# FPGA.net
KiCad netlist of a schematic drawn in Altium Designer
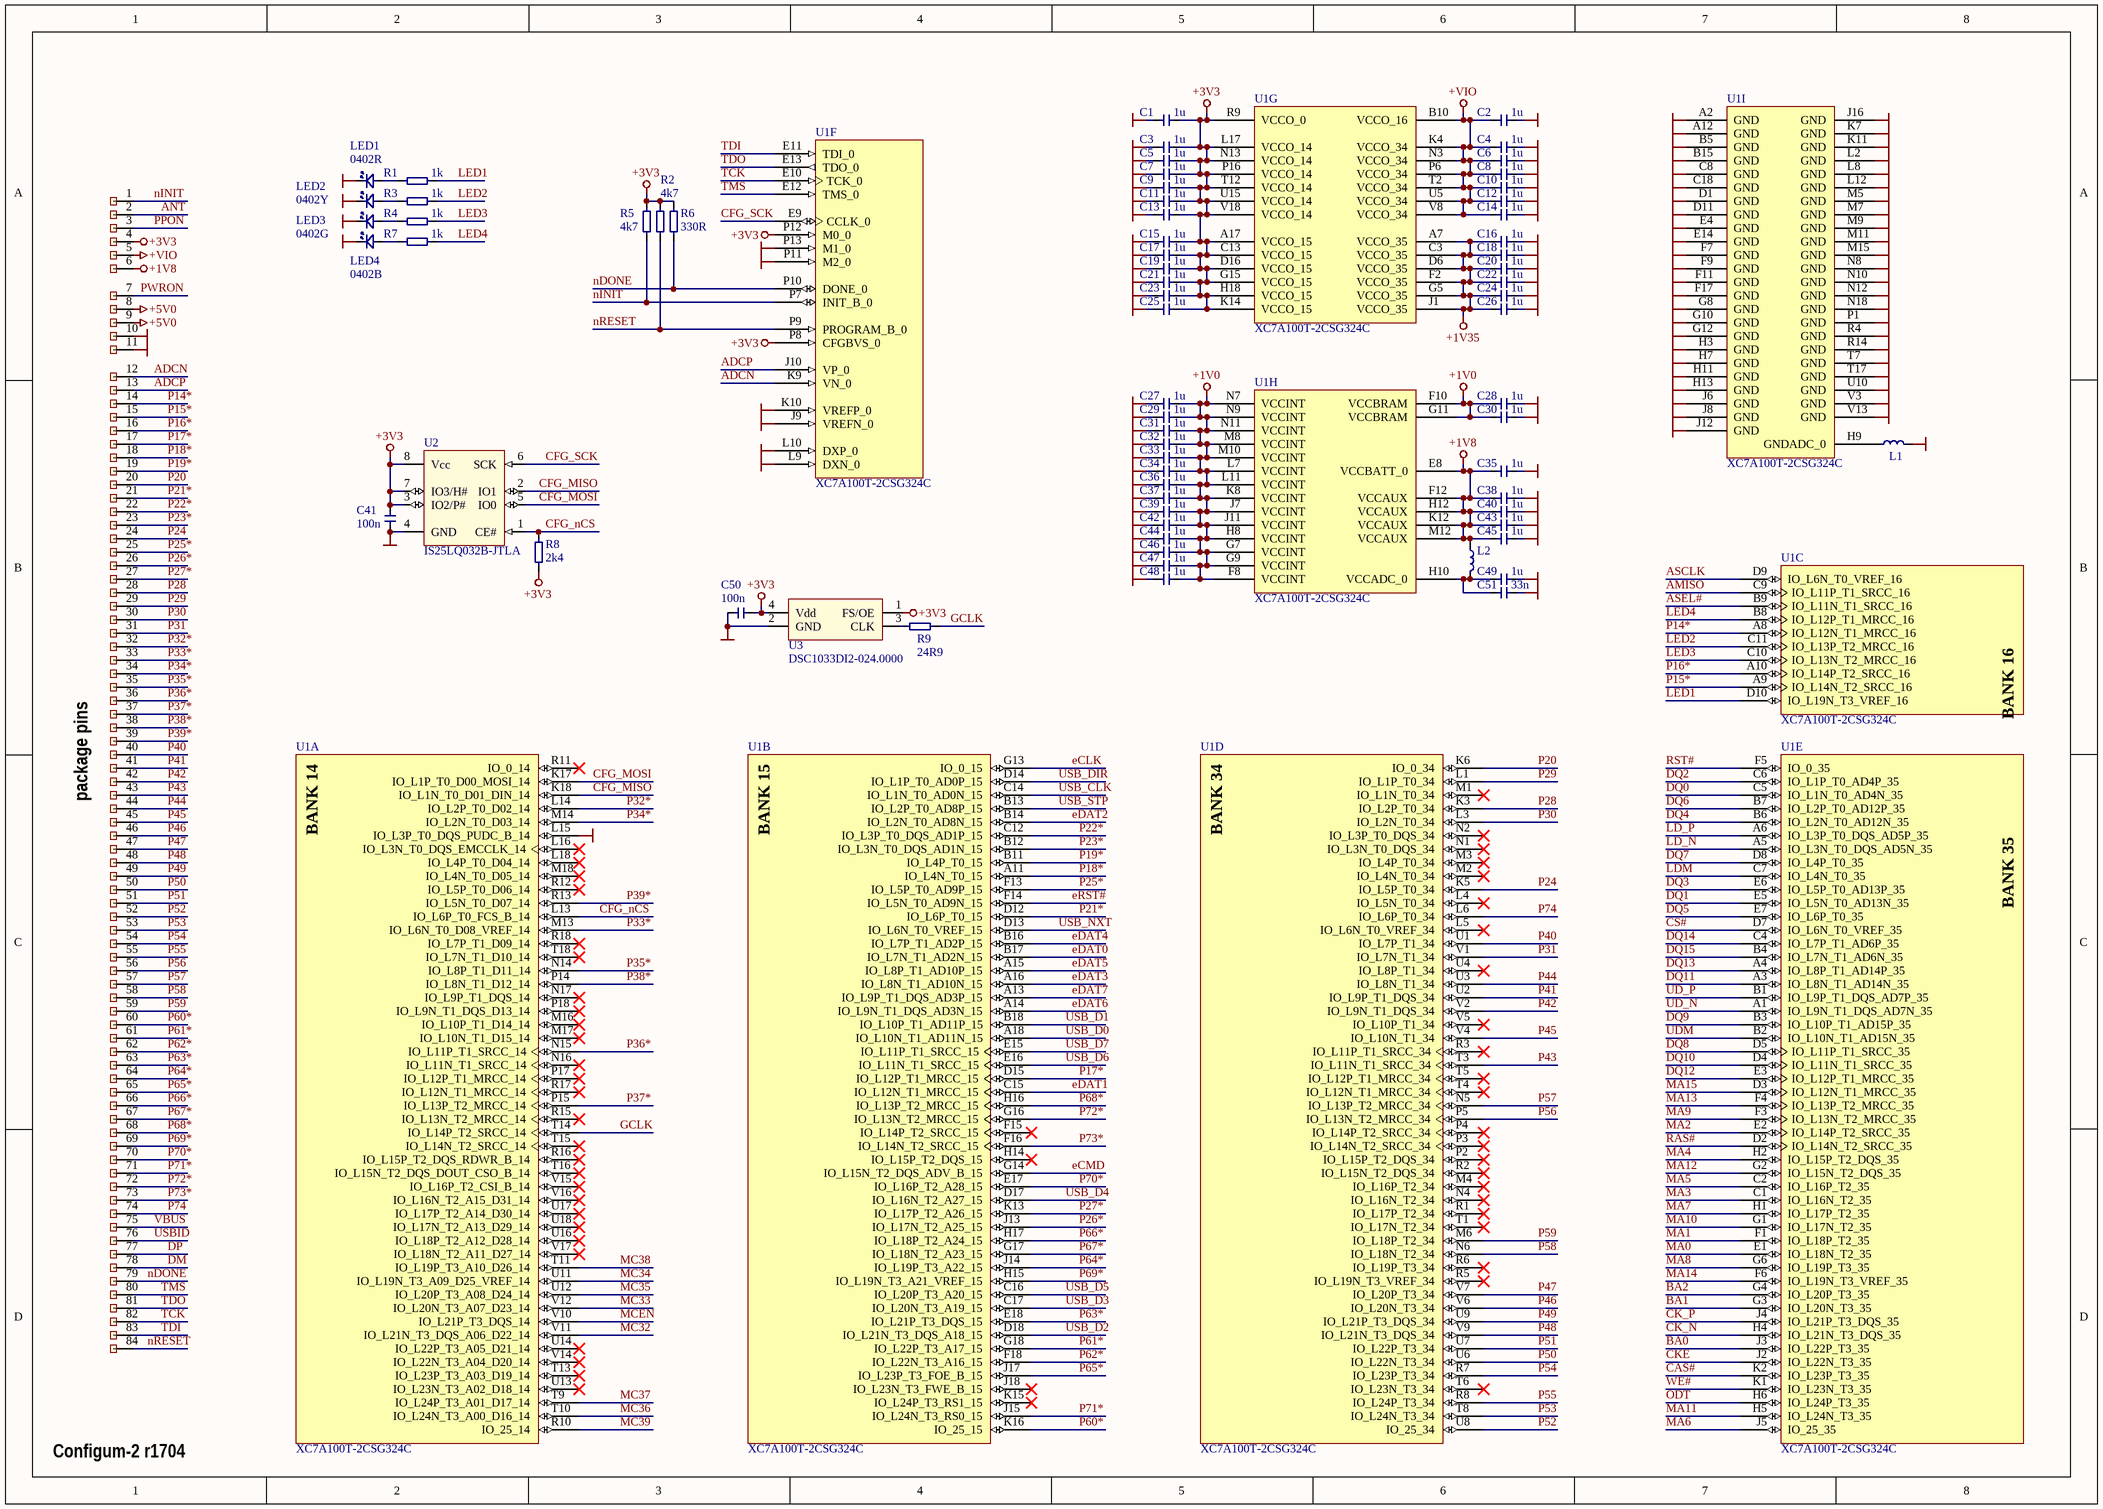
[diagram p0: FPGA.SchDoc]

(export (version "E")
  (design (tool "Eeschema 10.0.6"))
  (components
    (comp (ref "C1")
      (value "1u")
      (footprint "_0201")
      (description "Capacitor")
      (libsource (lib "Discretes") (part "Capacitor"))
    )
    (comp (ref "C2")
      (value "1u")
      (footprint "_0201")
      (description "Capacitor")
      (libsource (lib "Discretes") (part "Capacitor"))
    )
    (comp (ref "C3")
      (value "1u")
      (footprint "_0201")
      (description "Capacitor")
      (libsource (lib "Discretes") (part "Capacitor"))
    )
    (comp (ref "C4")
      (value "1u")
      (footprint "_0201")
      (description "Capacitor")
      (libsource (lib "Discretes") (part "Capacitor"))
    )
    (comp (ref "C5")
      (value "1u")
      (footprint "_0201")
      (description "Capacitor")
      (libsource (lib "Discretes") (part "Capacitor"))
    )
    (comp (ref "C6")
      (value "1u")
      (footprint "_0201")
      (description "Capacitor")
      (libsource (lib "Discretes") (part "Capacitor"))
    )
    (comp (ref "C7")
      (value "1u")
      (footprint "_0201")
      (description "Capacitor")
      (libsource (lib "Discretes") (part "Capacitor"))
    )
    (comp (ref "C8")
      (value "1u")
      (footprint "_0201")
      (description "Capacitor")
      (libsource (lib "Discretes") (part "Capacitor"))
    )
    (comp (ref "C9")
      (value "1u")
      (footprint "_0201")
      (description "Capacitor")
      (libsource (lib "Discretes") (part "Capacitor"))
    )
    (comp (ref "C10")
      (value "1u")
      (footprint "_0201")
      (description "Capacitor")
      (libsource (lib "Discretes") (part "Capacitor"))
    )
    (comp (ref "C11")
      (value "1u")
      (footprint "_0201")
      (description "Capacitor")
      (libsource (lib "Discretes") (part "Capacitor"))
    )
    (comp (ref "C12")
      (value "1u")
      (footprint "_0201")
      (description "Capacitor")
      (libsource (lib "Discretes") (part "Capacitor"))
    )
    (comp (ref "C13")
      (value "1u")
      (footprint "_0201")
      (description "Capacitor")
      (libsource (lib "Discretes") (part "Capacitor"))
    )
    (comp (ref "C14")
      (value "1u")
      (footprint "_0201")
      (description "Capacitor")
      (libsource (lib "Discretes") (part "Capacitor"))
    )
    (comp (ref "C15")
      (value "1u")
      (footprint "_0201")
      (description "Capacitor")
      (libsource (lib "Discretes") (part "Capacitor"))
    )
    (comp (ref "C16")
      (value "1u")
      (footprint "_0201")
      (description "Capacitor")
      (libsource (lib "Discretes") (part "Capacitor"))
    )
    (comp (ref "C17")
      (value "1u")
      (footprint "_0201")
      (description "Capacitor")
      (libsource (lib "Discretes") (part "Capacitor"))
    )
    (comp (ref "C18")
      (value "1u")
      (footprint "_0201")
      (description "Capacitor")
      (libsource (lib "Discretes") (part "Capacitor"))
    )
    (comp (ref "C19")
      (value "1u")
      (footprint "_0201")
      (description "Capacitor")
      (libsource (lib "Discretes") (part "Capacitor"))
    )
    (comp (ref "C20")
      (value "1u")
      (footprint "_0201")
      (description "Capacitor")
      (libsource (lib "Discretes") (part "Capacitor"))
    )
    (comp (ref "C21")
      (value "1u")
      (footprint "_0201")
      (description "Capacitor")
      (libsource (lib "Discretes") (part "Capacitor"))
    )
    (comp (ref "C22")
      (value "1u")
      (footprint "_0201")
      (description "Capacitor")
      (libsource (lib "Discretes") (part "Capacitor"))
    )
    (comp (ref "C23")
      (value "1u")
      (footprint "_0201")
      (description "Capacitor")
      (libsource (lib "Discretes") (part "Capacitor"))
    )
    (comp (ref "C24")
      (value "1u")
      (footprint "_0201")
      (description "Capacitor")
      (libsource (lib "Discretes") (part "Capacitor"))
    )
    (comp (ref "C25")
      (value "1u")
      (footprint "_0201")
      (description "Capacitor")
      (libsource (lib "Discretes") (part "Capacitor"))
    )
    (comp (ref "C26")
      (value "1u")
      (footprint "_0201")
      (description "Capacitor")
      (libsource (lib "Discretes") (part "Capacitor"))
    )
    (comp (ref "C27")
      (value "1u")
      (footprint "_0201")
      (description "Capacitor")
      (libsource (lib "Discretes") (part "Capacitor"))
    )
    (comp (ref "C28")
      (value "1u")
      (footprint "_0201")
      (description "Capacitor")
      (libsource (lib "Discretes") (part "Capacitor"))
    )
    (comp (ref "C29")
      (value "1u")
      (footprint "_0201")
      (description "Capacitor")
      (libsource (lib "Discretes") (part "Capacitor"))
    )
    (comp (ref "C30")
      (value "1u")
      (footprint "_0201")
      (description "Capacitor")
      (libsource (lib "Discretes") (part "Capacitor"))
    )
    (comp (ref "C31")
      (value "1u")
      (footprint "_0201")
      (description "Capacitor")
      (libsource (lib "Discretes") (part "Capacitor"))
    )
    (comp (ref "C32")
      (value "1u")
      (footprint "_0201")
      (description "Capacitor")
      (libsource (lib "Discretes") (part "Capacitor"))
    )
    (comp (ref "C33")
      (value "1u")
      (footprint "_0201")
      (description "Capacitor")
      (libsource (lib "Discretes") (part "Capacitor"))
    )
    (comp (ref "C34")
      (value "1u")
      (footprint "_0201")
      (description "Capacitor")
      (libsource (lib "Discretes") (part "Capacitor"))
    )
    (comp (ref "C35")
      (value "1u")
      (footprint "_0201")
      (description "Capacitor")
      (libsource (lib "Discretes") (part "Capacitor"))
    )
    (comp (ref "C36")
      (value "1u")
      (footprint "_0201")
      (description "Capacitor")
      (libsource (lib "Discretes") (part "Capacitor"))
    )
    (comp (ref "C37")
      (value "1u")
      (footprint "_0201")
      (description "Capacitor")
      (libsource (lib "Discretes") (part "Capacitor"))
    )
    (comp (ref "C38")
      (value "1u")
      (footprint "_0201")
      (description "Capacitor")
      (libsource (lib "Discretes") (part "Capacitor"))
    )
    (comp (ref "C39")
      (value "1u")
      (footprint "_0201")
      (description "Capacitor")
      (libsource (lib "Discretes") (part "Capacitor"))
    )
    (comp (ref "C40")
      (value "1u")
      (footprint "_0201")
      (description "Capacitor")
      (libsource (lib "Discretes") (part "Capacitor"))
    )
    (comp (ref "C41")
      (value "100n")
      (footprint "_0201")
      (description "Capacitor")
      (libsource (lib "Discretes") (part "Capacitor"))
    )
    (comp (ref "C42")
      (value "1u")
      (footprint "_0201")
      (description "Capacitor")
      (libsource (lib "Discretes") (part "Capacitor"))
    )
    (comp (ref "C43")
      (value "1u")
      (footprint "_0201")
      (description "Capacitor")
      (libsource (lib "Discretes") (part "Capacitor"))
    )
    (comp (ref "C44")
      (value "1u")
      (footprint "_0201")
      (description "Capacitor")
      (libsource (lib "Discretes") (part "Capacitor"))
    )
    (comp (ref "C45")
      (value "1u")
      (footprint "_0201")
      (description "Capacitor")
      (libsource (lib "Discretes") (part "Capacitor"))
    )
    (comp (ref "C46")
      (value "1u")
      (footprint "_0201")
      (description "Capacitor")
      (libsource (lib "Discretes") (part "Capacitor"))
    )
    (comp (ref "C47")
      (value "1u")
      (footprint "_0201")
      (description "Capacitor")
      (libsource (lib "Discretes") (part "Capacitor"))
    )
    (comp (ref "C48")
      (value "1u")
      (footprint "_0201")
      (description "Capacitor")
      (libsource (lib "Discretes") (part "Capacitor"))
    )
    (comp (ref "C49")
      (value "1u")
      (footprint "_0201")
      (description "Capacitor")
      (libsource (lib "Discretes") (part "Capacitor"))
    )
    (comp (ref "C50")
      (value "100n")
      (footprint "_0201")
      (description "Capacitor")
      (libsource (lib "Discretes") (part "Capacitor"))
    )
    (comp (ref "C51")
      (value "33n")
      (footprint "_0201")
      (description "Capacitor")
      (libsource (lib "Discretes") (part "Capacitor"))
    )
    (comp (ref "L1")
      (value "60R/100MHz")
      (footprint "_0201")
      (description "Inductor")
      (libsource (lib "Discretes") (part "Inductor"))
    )
    (comp (ref "L2")
      (value "60R/100MHz")
      (footprint "_0201")
      (description "Inductor")
      (libsource (lib "") (part "Inductor_1"))
    )
    (comp (ref "LED1")
      (value "0402R")
      (footprint "_0402+")
      (description "Light Emitting Diode")
      (libsource (lib "Discretes") (part "LED"))
    )
    (comp (ref "LED2")
      (value "0402Y")
      (footprint "_0402+")
      (description "Light Emitting Diode")
      (libsource (lib "Discretes") (part "LED"))
    )
    (comp (ref "LED3")
      (value "0402G")
      (footprint "_0402+")
      (description "Light Emitting Diode")
      (libsource (lib "Discretes") (part "LED"))
    )
    (comp (ref "LED4")
      (value "0402B")
      (footprint "_0402+")
      (description "Light Emitting Diode")
      (libsource (lib "Discretes") (part "LED"))
    )
    (comp (ref "PIN1")
      (value "Pin/Pad")
      (footprint "PLCC68 pin")
      (description "Single pin/pad")
      (libsource (lib "") (part "Pin/Pad_78"))
    )
    (comp (ref "PIN2")
      (value "Pin/Pad")
      (footprint "PLCC68 pin")
      (description "Single pin/pad")
      (libsource (lib "") (part "Pin/Pad_36"))
    )
    (comp (ref "PIN3")
      (value "Pin/Pad")
      (footprint "PLCC68 pin")
      (description "Single pin/pad")
      (libsource (lib "") (part "Pin/Pad_49"))
    )
    (comp (ref "PIN4")
      (value "Pin/Pad")
      (footprint "PLCC68 pin")
      (description "Single pin/pad")
      (libsource (lib "") (part "Pin/Pad_82"))
    )
    (comp (ref "PIN5")
      (value "Pin/Pad")
      (footprint "PLCC68 pin")
      (description "Single pin/pad")
      (libsource (lib "") (part "Pin/Pad_51"))
    )
    (comp (ref "PIN6")
      (value "Pin/Pad")
      (footprint "PLCC68 pin")
      (description "Single pin/pad")
      (libsource (lib "") (part "Pin/Pad_80"))
    )
    (comp (ref "PIN7")
      (value "Pin/Pad")
      (footprint "PLCC68 pin")
      (description "Single pin/pad")
      (libsource (lib "") (part "Pin/Pad_76"))
    )
    (comp (ref "PIN8")
      (value "Pin/Pad")
      (footprint "PLCC68 pin")
      (description "Single pin/pad")
      (libsource (lib "") (part "Pin/Pad_52"))
    )
    (comp (ref "PIN9")
      (value "Pin/Pad")
      (footprint "PLCC68 pin")
      (description "Single pin/pad")
      (libsource (lib "") (part "Pin/Pad_19"))
    )
    (comp (ref "PIN10")
      (value "Pin/Pad")
      (footprint "PLCC68 pin")
      (description "Single pin/pad")
      (libsource (lib "") (part "Pin/Pad_69"))
    )
    (comp (ref "PIN11")
      (value "Pin/Pad")
      (footprint "PLCC68 pin")
      (description "Single pin/pad")
      (libsource (lib "") (part "Pin/Pad_53"))
    )
    (comp (ref "PIN12")
      (value "Pin/Pad")
      (footprint "PLCC68 pin")
      (description "Single pin/pad")
      (libsource (lib "") (part "Pin/Pad_47"))
    )
    (comp (ref "PIN13")
      (value "Pin/Pad")
      (footprint "PLCC68 pin")
      (description "Single pin/pad")
      (libsource (lib "") (part "Pin/Pad_56"))
    )
    (comp (ref "PIN14")
      (value "Pin/Pad")
      (footprint "PLCC68 pin")
      (description "Single pin/pad")
      (libsource (lib "") (part "Pin/Pad_65"))
    )
    (comp (ref "PIN15")
      (value "Pin/Pad")
      (footprint "PLCC68 pin")
      (description "Single pin/pad")
      (libsource (lib "") (part "Pin/Pad_73"))
    )
    (comp (ref "PIN16")
      (value "Pin/Pad")
      (footprint "PLCC68 pin")
      (description "Single pin/pad")
      (libsource (lib "") (part "Pin/Pad_43"))
    )
    (comp (ref "PIN17")
      (value "Pin/Pad")
      (footprint "PLCC68 pin")
      (description "Single pin/pad")
      (libsource (lib "") (part "Pin/Pad_67"))
    )
    (comp (ref "PIN18")
      (value "Pin/Pad")
      (footprint "PLCC68 pin")
      (description "Single pin/pad")
      (libsource (lib "") (part "Pin/Pad_16"))
    )
    (comp (ref "PIN19")
      (value "Pin/Pad")
      (footprint "PLCC68 pin")
      (description "Single pin/pad")
      (libsource (lib "") (part "Pin/Pad_64"))
    )
    (comp (ref "PIN20")
      (value "Pin/Pad")
      (footprint "PLCC68 pin")
      (description "Single pin/pad")
      (libsource (lib "") (part "Pin/Pad_22"))
    )
    (comp (ref "PIN21")
      (value "Pin/Pad")
      (footprint "PLCC68 pin")
      (description "Single pin/pad")
      (libsource (lib "") (part "Pin/Pad_70"))
    )
    (comp (ref "PIN22")
      (value "Pin/Pad")
      (footprint "PLCC68 pin")
      (description "Single pin/pad")
      (libsource (lib "") (part "Pin/Pad_12"))
    )
    (comp (ref "PIN23")
      (value "Pin/Pad")
      (footprint "PLCC68 pin")
      (description "Single pin/pad")
      (libsource (lib "Connectors") (part "Pin/Pad"))
    )
    (comp (ref "PIN24")
      (value "Pin/Pad")
      (footprint "PLCC68 pin")
      (description "Single pin/pad")
      (libsource (lib "") (part "Pin/Pad_35"))
    )
    (comp (ref "PIN25")
      (value "Pin/Pad")
      (footprint "PLCC68 pin")
      (description "Single pin/pad")
      (libsource (lib "") (part "Pin/Pad_10"))
    )
    (comp (ref "PIN26")
      (value "Pin/Pad")
      (footprint "PLCC68 pin")
      (description "Single pin/pad")
      (libsource (lib "") (part "Pin/Pad_71"))
    )
    (comp (ref "PIN27")
      (value "Pin/Pad")
      (footprint "PLCC68 pin")
      (description "Single pin/pad")
      (libsource (lib "") (part "Pin/Pad_41"))
    )
    (comp (ref "PIN28")
      (value "Pin/Pad")
      (footprint "PLCC68 pin")
      (description "Single pin/pad")
      (libsource (lib "") (part "Pin/Pad_32"))
    )
    (comp (ref "PIN29")
      (value "Pin/Pad")
      (footprint "PLCC68 pin")
      (description "Single pin/pad")
      (libsource (lib "") (part "Pin/Pad_66"))
    )
    (comp (ref "PIN30")
      (value "Pin/Pad")
      (footprint "PLCC68 pin")
      (description "Single pin/pad")
      (libsource (lib "") (part "Pin/Pad_61"))
    )
    (comp (ref "PIN31")
      (value "Pin/Pad")
      (footprint "PLCC68 pin")
      (description "Single pin/pad")
      (libsource (lib "") (part "Pin/Pad_5"))
    )
    (comp (ref "PIN32")
      (value "Pin/Pad")
      (footprint "PLCC68 pin")
      (description "Single pin/pad")
      (libsource (lib "") (part "Pin/Pad_44"))
    )
    (comp (ref "PIN33")
      (value "Pin/Pad")
      (footprint "PLCC68 pin")
      (description "Single pin/pad")
      (libsource (lib "") (part "Pin/Pad_60"))
    )
    (comp (ref "PIN34")
      (value "Pin/Pad")
      (footprint "PLCC68 pin")
      (description "Single pin/pad")
      (libsource (lib "") (part "Pin/Pad_1"))
    )
    (comp (ref "PIN35")
      (value "Pin/Pad")
      (footprint "PLCC68 pin")
      (description "Single pin/pad")
      (libsource (lib "") (part "Pin/Pad_55"))
    )
    (comp (ref "PIN36")
      (value "Pin/Pad")
      (footprint "PLCC68 pin")
      (description "Single pin/pad")
      (libsource (lib "") (part "Pin/Pad_40"))
    )
    (comp (ref "PIN37")
      (value "Pin/Pad")
      (footprint "PLCC68 pin")
      (description "Single pin/pad")
      (libsource (lib "") (part "Pin/Pad_29"))
    )
    (comp (ref "PIN38")
      (value "Pin/Pad")
      (footprint "PLCC68 pin")
      (description "Single pin/pad")
      (libsource (lib "") (part "Pin/Pad_26"))
    )
    (comp (ref "PIN39")
      (value "Pin/Pad")
      (footprint "PLCC68 pin")
      (description "Single pin/pad")
      (libsource (lib "") (part "Pin/Pad_6"))
    )
    (comp (ref "PIN40")
      (value "Pin/Pad")
      (footprint "PLCC68 pin")
      (description "Single pin/pad")
      (libsource (lib "") (part "Pin/Pad_20"))
    )
    (comp (ref "PIN41")
      (value "Pin/Pad")
      (footprint "PLCC68 pin")
      (description "Single pin/pad")
      (libsource (lib "") (part "Pin/Pad_46"))
    )
    (comp (ref "PIN42")
      (value "Pin/Pad")
      (footprint "PLCC68 pin")
      (description "Single pin/pad")
      (libsource (lib "") (part "Pin/Pad_63"))
    )
    (comp (ref "PIN43")
      (value "Pin/Pad")
      (footprint "PLCC68 pin")
      (description "Single pin/pad")
      (libsource (lib "") (part "Pin/Pad_68"))
    )
    (comp (ref "PIN44")
      (value "Pin/Pad")
      (footprint "PLCC68 pin")
      (description "Single pin/pad")
      (libsource (lib "") (part "Pin/Pad_42"))
    )
    (comp (ref "PIN45")
      (value "Pin/Pad")
      (footprint "PLCC68 pin")
      (description "Single pin/pad")
      (libsource (lib "") (part "Pin/Pad_83"))
    )
    (comp (ref "PIN46")
      (value "Pin/Pad")
      (footprint "PLCC68 pin")
      (description "Single pin/pad")
      (libsource (lib "") (part "Pin/Pad_14"))
    )
    (comp (ref "PIN47")
      (value "Pin/Pad")
      (footprint "PLCC68 pin")
      (description "Single pin/pad")
      (libsource (lib "") (part "Pin/Pad_48"))
    )
    (comp (ref "PIN48")
      (value "Pin/Pad")
      (footprint "PLCC68 pin")
      (description "Single pin/pad")
      (libsource (lib "") (part "Pin/Pad_37"))
    )
    (comp (ref "PIN49")
      (value "Pin/Pad")
      (footprint "PLCC68 pin")
      (description "Single pin/pad")
      (libsource (lib "") (part "Pin/Pad_2"))
    )
    (comp (ref "PIN50")
      (value "Pin/Pad")
      (footprint "PLCC68 pin")
      (description "Single pin/pad")
      (libsource (lib "") (part "Pin/Pad_24"))
    )
    (comp (ref "PIN51")
      (value "Pin/Pad")
      (footprint "PLCC68 pin")
      (description "Single pin/pad")
      (libsource (lib "") (part "Pin/Pad_81"))
    )
    (comp (ref "PIN52")
      (value "Pin/Pad")
      (footprint "PLCC68 pin")
      (description "Single pin/pad")
      (libsource (lib "") (part "Pin/Pad_50"))
    )
    (comp (ref "PIN53")
      (value "Pin/Pad")
      (footprint "PLCC68 pin")
      (description "Single pin/pad")
      (libsource (lib "") (part "Pin/Pad_28"))
    )
    (comp (ref "PIN54")
      (value "Pin/Pad")
      (footprint "PLCC68 pin")
      (description "Single pin/pad")
      (libsource (lib "") (part "Pin/Pad_45"))
    )
    (comp (ref "PIN55")
      (value "Pin/Pad")
      (footprint "PLCC68 pin")
      (description "Single pin/pad")
      (libsource (lib "") (part "Pin/Pad_58"))
    )
    (comp (ref "PIN56")
      (value "Pin/Pad")
      (footprint "PLCC68 pin")
      (description "Single pin/pad")
      (libsource (lib "") (part "Pin/Pad_18"))
    )
    (comp (ref "PIN57")
      (value "Pin/Pad")
      (footprint "PLCC68 pin")
      (description "Single pin/pad")
      (libsource (lib "") (part "Pin/Pad_13"))
    )
    (comp (ref "PIN58")
      (value "Pin/Pad")
      (footprint "PLCC68 pin")
      (description "Single pin/pad")
      (libsource (lib "") (part "Pin/Pad_4"))
    )
    (comp (ref "PIN59")
      (value "Pin/Pad")
      (footprint "PLCC68 pin")
      (description "Single pin/pad")
      (libsource (lib "") (part "Pin/Pad_75"))
    )
    (comp (ref "PIN60")
      (value "Pin/Pad")
      (footprint "PLCC68 pin")
      (description "Single pin/pad")
      (libsource (lib "") (part "Pin/Pad_11"))
    )
    (comp (ref "PIN61")
      (value "Pin/Pad")
      (footprint "PLCC68 pin")
      (description "Single pin/pad")
      (libsource (lib "") (part "Pin/Pad_77"))
    )
    (comp (ref "PIN62")
      (value "Pin/Pad")
      (footprint "PLCC68 pin")
      (description "Single pin/pad")
      (libsource (lib "") (part "Pin/Pad_15"))
    )
    (comp (ref "PIN63")
      (value "Pin/Pad")
      (footprint "PLCC68 pin")
      (description "Single pin/pad")
      (libsource (lib "") (part "Pin/Pad_7"))
    )
    (comp (ref "PIN64")
      (value "Pin/Pad")
      (footprint "PLCC68 pin")
      (description "Single pin/pad")
      (libsource (lib "") (part "Pin/Pad_30"))
    )
    (comp (ref "PIN65")
      (value "Pin/Pad")
      (footprint "PLCC68 pin")
      (description "Single pin/pad")
      (libsource (lib "") (part "Pin/Pad_21"))
    )
    (comp (ref "PIN66")
      (value "Pin/Pad")
      (footprint "PLCC68 pin")
      (description "Single pin/pad")
      (libsource (lib "") (part "Pin/Pad_33"))
    )
    (comp (ref "PIN67")
      (value "Pin/Pad")
      (footprint "PLCC68 pin")
      (description "Single pin/pad")
      (libsource (lib "") (part "Pin/Pad_9"))
    )
    (comp (ref "PIN68")
      (value "Pin/Pad")
      (footprint "PLCC68 pin")
      (description "Single pin/pad")
      (libsource (lib "") (part "Pin/Pad_17"))
    )
    (comp (ref "PIN69")
      (value "Pin/Pad")
      (footprint "PLCC68 pin")
      (description "Single pin/pad")
      (libsource (lib "") (part "Pin/Pad_27"))
    )
    (comp (ref "PIN70")
      (value "Pin/Pad")
      (footprint "PLCC68 pin")
      (description "Single pin/pad")
      (libsource (lib "") (part "Pin/Pad_38"))
    )
    (comp (ref "PIN71")
      (value "Pin/Pad")
      (footprint "PLCC68 pin")
      (description "Single pin/pad")
      (libsource (lib "") (part "Pin/Pad_59"))
    )
    (comp (ref "PIN72")
      (value "Pin/Pad")
      (footprint "PLCC68 pin")
      (description "Single pin/pad")
      (libsource (lib "") (part "Pin/Pad_23"))
    )
    (comp (ref "PIN73")
      (value "Pin/Pad")
      (footprint "PLCC68 pin")
      (description "Single pin/pad")
      (libsource (lib "") (part "Pin/Pad_62"))
    )
    (comp (ref "PIN74")
      (value "Pin/Pad")
      (footprint "PLCC68 pin")
      (description "Single pin/pad")
      (libsource (lib "") (part "Pin/Pad_34"))
    )
    (comp (ref "PIN75")
      (value "Pin/Pad")
      (footprint "PLCC68 pin")
      (description "Single pin/pad")
      (libsource (lib "") (part "Pin/Pad_54"))
    )
    (comp (ref "PIN76")
      (value "Pin/Pad")
      (footprint "PLCC68 pin")
      (description "Single pin/pad")
      (libsource (lib "") (part "Pin/Pad_57"))
    )
    (comp (ref "PIN77")
      (value "Pin/Pad")
      (footprint "PLCC68 pin")
      (description "Single pin/pad")
      (libsource (lib "") (part "Pin/Pad_39"))
    )
    (comp (ref "PIN78")
      (value "Pin/Pad")
      (footprint "PLCC68 pin")
      (description "Single pin/pad")
      (libsource (lib "") (part "Pin/Pad_79"))
    )
    (comp (ref "PIN79")
      (value "Pin/Pad")
      (footprint "PLCC68 pin")
      (description "Single pin/pad")
      (libsource (lib "") (part "Pin/Pad_8"))
    )
    (comp (ref "PIN80")
      (value "Pin/Pad")
      (footprint "PLCC68 pin")
      (description "Single pin/pad")
      (libsource (lib "") (part "Pin/Pad_31"))
    )
    (comp (ref "PIN81")
      (value "Pin/Pad")
      (footprint "PLCC68 pin")
      (description "Single pin/pad")
      (libsource (lib "") (part "Pin/Pad_72"))
    )
    (comp (ref "PIN82")
      (value "Pin/Pad")
      (footprint "PLCC68 pin")
      (description "Single pin/pad")
      (libsource (lib "") (part "Pin/Pad_3"))
    )
    (comp (ref "PIN83")
      (value "Pin/Pad")
      (footprint "PLCC68 pin")
      (description "Single pin/pad")
      (libsource (lib "") (part "Pin/Pad_74"))
    )
    (comp (ref "PIN84")
      (value "Pin/Pad")
      (footprint "PLCC68 pin")
      (description "Single pin/pad")
      (libsource (lib "") (part "Pin/Pad_25"))
    )
    (comp (ref "R1")
      (value "1k")
      (footprint "_0201")
      (description "Resistor")
      (libsource (lib "Discretes") (part "Resistor"))
    )
    (comp (ref "R2")
      (value "4k7")
      (footprint "_0201")
      (description "Resistor")
      (libsource (lib "Discretes") (part "Resistor"))
    )
    (comp (ref "R3")
      (value "1k")
      (footprint "_0201")
      (description "Resistor")
      (libsource (lib "Discretes") (part "Resistor"))
    )
    (comp (ref "R4")
      (value "1k")
      (footprint "_0201")
      (description "Resistor")
      (libsource (lib "Discretes") (part "Resistor"))
    )
    (comp (ref "R5")
      (value "4k7")
      (footprint "_0201")
      (description "Resistor")
      (libsource (lib "Discretes") (part "Resistor"))
    )
    (comp (ref "R6")
      (value "330R")
      (footprint "_0201")
      (description "Resistor")
      (libsource (lib "") (part "Resistor_2"))
    )
    (comp (ref "R7")
      (value "1k")
      (footprint "_0201")
      (description "Resistor")
      (libsource (lib "Discretes") (part "Resistor"))
    )
    (comp (ref "R8")
      (value "2k4")
      (footprint "_0201")
      (description "Resistor")
      (libsource (lib "") (part "Resistor_1"))
    )
    (comp (ref "R9")
      (value "24R9")
      (footprint "_0201")
      (description "Resistor")
      (libsource (lib "") (part "Resistor_1"))
    )
    (comp (ref "U1")
      (value "XC7A100T-2CSG324C")
      (footprint "CSG324")
      (description "Artix-7 FPGA, 210 User I/Os, 0 GTP, 324-Ball BGA, Speed Grade 2, Commercial Grade, Pb-Free")
      (fields (field (name "GENERIC PART NUMBER") "XC7A100T") (field (name "MANUFACTURER") "Xilinx"))
      (libsource (lib "Xilinx Artix-7") (part "XC7A100T-2CSG324C"))
    )
    (comp (ref "U2")
      (value "IS25LQ032B-JTLA")
      (footprint "SON80P300X60_HS-9L")
      (description "Standard 8-pin SPI flash memory")
      (libsource (lib "IC Other Functions") (part "SPI Flash 8pin"))
    )
    (comp (ref "U3")
      (value "DSC1033DI2-024.0000")
      (footprint "Osc 25x20 (4)")
      (description "32kHz –100MHz CMEMS Oscillator")
      (fields (field (name "MANUFACTURER") "Silicon Labs"))
      (libsource (lib "IC Other Functions") (part "Si50x"))
    )
  )
  (nets
    (net (code "1") (name "+1V0") (class "Default")
      (node (ref "C27") (pin "1") (pintype "passive"))
      (node (ref "C28") (pin "2") (pintype "passive"))
      (node (ref "C29") (pin "1") (pintype "passive"))
      (node (ref "C30") (pin "2") (pintype "passive"))
      (node (ref "C31") (pin "1") (pintype "passive"))
      (node (ref "C32") (pin "1") (pintype "passive"))
      (node (ref "C33") (pin "1") (pintype "passive"))
      (node (ref "C34") (pin "1") (pintype "passive"))
      (node (ref "C36") (pin "1") (pintype "passive"))
      (node (ref "C37") (pin "1") (pintype "passive"))
      (node (ref "C39") (pin "1") (pintype "passive"))
      (node (ref "C42") (pin "1") (pintype "passive"))
      (node (ref "C44") (pin "1") (pintype "passive"))
      (node (ref "C46") (pin "1") (pintype "passive"))
      (node (ref "C47") (pin "1") (pintype "passive"))
      (node (ref "C48") (pin "1") (pintype "passive"))
      (node (ref "U1") (pin "F10") (pinfunction "VCCBRAM_F10") (pintype "power_in"))
      (node (ref "U1") (pin "F8") (pinfunction "VCCINT_F8") (pintype "power_in"))
      (node (ref "U1") (pin "G11") (pinfunction "VCCBRAM_G11") (pintype "power_in"))
      (node (ref "U1") (pin "G7") (pinfunction "VCCINT_G7") (pintype "power_in"))
      (node (ref "U1") (pin "G9") (pinfunction "VCCINT_G9") (pintype "power_in"))
      (node (ref "U1") (pin "H8") (pinfunction "VCCINT_H8") (pintype "power_in"))
      (node (ref "U1") (pin "J11") (pinfunction "VCCINT_J11") (pintype "power_in"))
      (node (ref "U1") (pin "J7") (pinfunction "VCCINT_J7") (pintype "power_in"))
      (node (ref "U1") (pin "K8") (pinfunction "VCCINT_K8") (pintype "power_in"))
      (node (ref "U1") (pin "L11") (pinfunction "VCCINT_L11") (pintype "power_in"))
      (node (ref "U1") (pin "L7") (pinfunction "VCCINT_L7") (pintype "power_in"))
      (node (ref "U1") (pin "M10") (pinfunction "VCCINT_M10") (pintype "power_in"))
      (node (ref "U1") (pin "M8") (pinfunction "VCCINT_M8") (pintype "power_in"))
      (node (ref "U1") (pin "N11") (pinfunction "VCCINT_N11") (pintype "power_in"))
      (node (ref "U1") (pin "N7") (pinfunction "VCCINT_N7") (pintype "power_in"))
      (node (ref "U1") (pin "N9") (pinfunction "VCCINT_N9") (pintype "power_in"))
    )
    (net (code "2") (name "+1V8") (class "Default")
      (node (ref "C35") (pin "2") (pintype "passive"))
      (node (ref "C38") (pin "2") (pintype "passive"))
      (node (ref "C40") (pin "2") (pintype "passive"))
      (node (ref "C43") (pin "2") (pintype "passive"))
      (node (ref "C45") (pin "2") (pintype "passive"))
      (node (ref "L2") (pin "2") (pintype "passive"))
      (node (ref "PIN6") (pin "6") (pintype "passive"))
      (node (ref "U1") (pin "E8") (pinfunction "VCCBATT_0_E8") (pintype "power_in"))
      (node (ref "U1") (pin "F12") (pinfunction "VCCAUX_F12") (pintype "power_in"))
      (node (ref "U1") (pin "H12") (pinfunction "VCCAUX_H12") (pintype "power_in"))
      (node (ref "U1") (pin "K12") (pinfunction "VCCAUX_K12") (pintype "power_in"))
      (node (ref "U1") (pin "M12") (pinfunction "VCCAUX_M12") (pintype "power_in"))
    )
    (net (code "3") (name "+1V35") (class "Default")
      (node (ref "C16") (pin "2") (pintype "passive"))
      (node (ref "C18") (pin "2") (pintype "passive"))
      (node (ref "C20") (pin "2") (pintype "passive"))
      (node (ref "C22") (pin "2") (pintype "passive"))
      (node (ref "C24") (pin "2") (pintype "passive"))
      (node (ref "C26") (pin "2") (pintype "passive"))
      (node (ref "U1") (pin "A7") (pinfunction "VCCO_35_A7") (pintype "power_in"))
      (node (ref "U1") (pin "C3") (pinfunction "VCCO_35_C3") (pintype "power_in"))
      (node (ref "U1") (pin "D6") (pinfunction "VCCO_35_D6") (pintype "power_in"))
      (node (ref "U1") (pin "F2") (pinfunction "VCCO_35_F2") (pintype "power_in"))
      (node (ref "U1") (pin "G5") (pinfunction "VCCO_35_G5") (pintype "power_in"))
      (node (ref "U1") (pin "J1") (pinfunction "VCCO_35_J1") (pintype "power_in"))
    )
    (net (code "4") (name "+3V3") (class "Default")
      (node (ref "C1") (pin "1") (pintype "passive"))
      (node (ref "C11") (pin "1") (pintype "passive"))
      (node (ref "C13") (pin "1") (pintype "passive"))
      (node (ref "C15") (pin "1") (pintype "passive"))
      (node (ref "C17") (pin "1") (pintype "passive"))
      (node (ref "C19") (pin "1") (pintype "passive"))
      (node (ref "C21") (pin "1") (pintype "passive"))
      (node (ref "C23") (pin "1") (pintype "passive"))
      (node (ref "C25") (pin "1") (pintype "passive"))
      (node (ref "C3") (pin "1") (pintype "passive"))
      (node (ref "C41") (pin "2") (pintype "passive"))
      (node (ref "C5") (pin "1") (pintype "passive"))
      (node (ref "C50") (pin "1") (pintype "passive"))
      (node (ref "C7") (pin "1") (pintype "passive"))
      (node (ref "C9") (pin "1") (pintype "passive"))
      (node (ref "PIN4") (pin "4") (pintype "passive"))
      (node (ref "R2") (pin "2") (pintype "passive"))
      (node (ref "R5") (pin "2") (pintype "passive"))
      (node (ref "R6") (pin "1") (pintype "passive"))
      (node (ref "R8") (pin "1") (pintype "passive"))
      (node (ref "U1") (pin "A17") (pinfunction "VCCO_15_A17") (pintype "power_in"))
      (node (ref "U1") (pin "C13") (pinfunction "VCCO_15_C13") (pintype "power_in"))
      (node (ref "U1") (pin "D16") (pinfunction "VCCO_15_D16") (pintype "power_in"))
      (node (ref "U1") (pin "G15") (pinfunction "VCCO_15_G15") (pintype "power_in"))
      (node (ref "U1") (pin "H18") (pinfunction "VCCO_15_H18") (pintype "power_in"))
      (node (ref "U1") (pin "K14") (pinfunction "VCCO_15_K14") (pintype "power_in"))
      (node (ref "U1") (pin "L17") (pinfunction "VCCO_14_L17") (pintype "power_in"))
      (node (ref "U1") (pin "N13") (pinfunction "VCCO_14_N13") (pintype "power_in"))
      (node (ref "U1") (pin "P12") (pinfunction "M0_0_P12") (pintype "input"))
      (node (ref "U1") (pin "P16") (pinfunction "VCCO_14_P16") (pintype "power_in"))
      (node (ref "U1") (pin "P8") (pinfunction "CFGBVS_0_P8") (pintype "input"))
      (node (ref "U1") (pin "R9") (pinfunction "VCCO_0_R9") (pintype "power_in"))
      (node (ref "U1") (pin "T12") (pinfunction "VCCO_14_T12") (pintype "power_in"))
      (node (ref "U1") (pin "U15") (pinfunction "VCCO_14_U15") (pintype "power_in"))
      (node (ref "U1") (pin "V18") (pinfunction "VCCO_14_V18") (pintype "power_in"))
      (node (ref "U2") (pin "3") (pinfunction "IO2/P#_3") (pintype "bidirectional"))
      (node (ref "U2") (pin "7") (pinfunction "IO3/H#_7") (pintype "bidirectional"))
      (node (ref "U2") (pin "8") (pinfunction "Vcc_8") (pintype "power_in"))
      (node (ref "U3") (pin "1") (pinfunction "FS/OE_1") (pintype "passive"))
      (node (ref "U3") (pin "4") (pinfunction "Vdd_4") (pintype "passive"))
    )
    (net (code "5") (name "+5V0") (class "Default")
      (node (ref "PIN8") (pin "8") (pintype "passive"))
      (node (ref "PIN9") (pin "9") (pintype "passive"))
    )
    (net (code "6") (name "+VIO") (class "Default")
      (node (ref "C10") (pin "2") (pintype "passive"))
      (node (ref "C12") (pin "2") (pintype "passive"))
      (node (ref "C14") (pin "2") (pintype "passive"))
      (node (ref "C2") (pin "2") (pintype "passive"))
      (node (ref "C4") (pin "2") (pintype "passive"))
      (node (ref "C6") (pin "2") (pintype "passive"))
      (node (ref "C8") (pin "2") (pintype "passive"))
      (node (ref "PIN5") (pin "5") (pintype "passive"))
      (node (ref "U1") (pin "B10") (pinfunction "VCCO_16_B10") (pintype "power_in"))
      (node (ref "U1") (pin "K4") (pinfunction "VCCO_34_K4") (pintype "power_in"))
      (node (ref "U1") (pin "N3") (pinfunction "VCCO_34_N3") (pintype "power_in"))
      (node (ref "U1") (pin "P6") (pinfunction "VCCO_34_P6") (pintype "power_in"))
      (node (ref "U1") (pin "T2") (pinfunction "VCCO_34_T2") (pintype "power_in"))
      (node (ref "U1") (pin "U5") (pinfunction "VCCO_34_U5") (pintype "power_in"))
      (node (ref "U1") (pin "V8") (pinfunction "VCCO_34_V8") (pintype "power_in"))
    )
    (net (code "7") (name "/ADCN") (class "Default")
      (node (ref "PIN12") (pin "12") (pintype "passive"))
      (node (ref "U1") (pin "K9") (pinfunction "VN_0_K9") (pintype "input"))
    )
    (net (code "8") (name "/ADCP") (class "Default")
      (node (ref "PIN13") (pin "13") (pintype "passive"))
      (node (ref "U1") (pin "J10") (pinfunction "VP_0_J10") (pintype "input"))
    )
    (net (code "9") (name "/AMISO") (class "Default")
      (node (ref "U1") (pin "C9") (pinfunction "IO_L11P_T1_SRCC_16_C9") (pintype "bidirectional"))
    )
    (net (code "10") (name "/ANT") (class "Default") (node (ref "PIN2") (pin "2") (pintype "passive")))
    (net (code "11") (name "/ASCLK") (class "Default")
      (node (ref "U1") (pin "D9") (pinfunction "IO_L6N_T0_VREF_16_D9") (pintype "bidirectional"))
    )
    (net (code "12") (name "/ASEL#") (class "Default")
      (node (ref "U1") (pin "B9") (pinfunction "IO_L11N_T1_SRCC_16_B9") (pintype "bidirectional"))
    )
    (net (code "13") (name "/BA0") (class "Default")
      (node (ref "U1") (pin "J3") (pinfunction "IO_L22P_T3_35_J3") (pintype "bidirectional"))
    )
    (net (code "14") (name "/BA1") (class "Default")
      (node (ref "U1") (pin "G3") (pinfunction "IO_L20N_T3_35_G3") (pintype "bidirectional"))
    )
    (net (code "15") (name "/BA2") (class "Default")
      (node (ref "U1") (pin "G4") (pinfunction "IO_L20P_T3_35_G4") (pintype "bidirectional"))
    )
    (net (code "16") (name "/CAS#") (class "Default")
      (node (ref "U1") (pin "K2") (pinfunction "IO_L23P_T3_35_K2") (pintype "bidirectional"))
    )
    (net (code "17") (name "/CFG_MISO") (class "Default")
      (node (ref "U1") (pin "K18") (pinfunction "IO_L1N_T0_D01_DIN_14_K18") (pintype "bidirectional"))
      (node (ref "U2") (pin "2") (pinfunction "IO1_2") (pintype "bidirectional"))
    )
    (net (code "18") (name "/CFG_MOSI") (class "Default")
      (node (ref "U1") (pin "K17") (pinfunction "IO_L1P_T0_D00_MOSI_14_K17") (pintype "bidirectional"))
      (node (ref "U2") (pin "5") (pinfunction "IO0_5") (pintype "bidirectional"))
    )
    (net (code "19") (name "/CFG_SCK") (class "Default")
      (node (ref "U1") (pin "E9") (pinfunction "CCLK_0_E9") (pintype "bidirectional"))
      (node (ref "U2") (pin "6") (pinfunction "SCK_6") (pintype "input"))
    )
    (net (code "20") (name "/CFG_nCS") (class "Default")
      (node (ref "R8") (pin "2") (pintype "passive"))
      (node (ref "U1") (pin "L13") (pinfunction "IO_L6P_T0_FCS_B_14_L13") (pintype "bidirectional"))
      (node (ref "U2") (pin "1") (pinfunction "CE#_1") (pintype "input"))
    )
    (net (code "21") (name "/CKE") (class "Default")
      (node (ref "U1") (pin "J2") (pinfunction "IO_L22N_T3_35_J2") (pintype "bidirectional"))
    )
    (net (code "22") (name "/CK_N") (class "Default")
      (node (ref "U1") (pin "H4") (pinfunction "IO_L21N_T3_DQS_35_H4") (pintype "bidirectional"))
    )
    (net (code "23") (name "/CK_P") (class "Default")
      (node (ref "U1") (pin "J4") (pinfunction "IO_L21P_T3_DQS_35_J4") (pintype "bidirectional"))
    )
    (net (code "24") (name "/CS#") (class "Default")
      (node (ref "U1") (pin "D7") (pinfunction "IO_L6N_T0_VREF_35_D7") (pintype "bidirectional"))
    )
    (net (code "25") (name "/DM") (class "Default") (node (ref "PIN78") (pin "78") (pintype "passive")))
    (net (code "26") (name "/DP") (class "Default") (node (ref "PIN77") (pin "77") (pintype "passive")))
    (net (code "27") (name "/DQ0") (class "Default")
      (node (ref "U1") (pin "C5") (pinfunction "IO_L1N_T0_AD4N_35_C5") (pintype "bidirectional"))
    )
    (net (code "28") (name "/DQ1") (class "Default")
      (node (ref "U1") (pin "E5") (pinfunction "IO_L5N_T0_AD13N_35_E5") (pintype "bidirectional"))
    )
    (net (code "29") (name "/DQ2") (class "Default")
      (node (ref "U1") (pin "C6") (pinfunction "IO_L1P_T0_AD4P_35_C6") (pintype "bidirectional"))
    )
    (net (code "30") (name "/DQ3") (class "Default")
      (node (ref "U1") (pin "E6") (pinfunction "IO_L5P_T0_AD13P_35_E6") (pintype "bidirectional"))
    )
    (net (code "31") (name "/DQ4") (class "Default")
      (node (ref "U1") (pin "B6") (pinfunction "IO_L2N_T0_AD12N_35_B6") (pintype "bidirectional"))
    )
    (net (code "32") (name "/DQ5") (class "Default")
      (node (ref "U1") (pin "E7") (pinfunction "IO_L6P_T0_35_E7") (pintype "bidirectional"))
    )
    (net (code "33") (name "/DQ6") (class "Default")
      (node (ref "U1") (pin "B7") (pinfunction "IO_L2P_T0_AD12P_35_B7") (pintype "bidirectional"))
    )
    (net (code "34") (name "/DQ7") (class "Default")
      (node (ref "U1") (pin "D8") (pinfunction "IO_L4P_T0_35_D8") (pintype "bidirectional"))
    )
    (net (code "35") (name "/DQ8") (class "Default")
      (node (ref "U1") (pin "D5") (pinfunction "IO_L11P_T1_SRCC_35_D5") (pintype "bidirectional"))
    )
    (net (code "36") (name "/DQ9") (class "Default")
      (node (ref "U1") (pin "B3") (pinfunction "IO_L10P_T1_AD15P_35_B3") (pintype "bidirectional"))
    )
    (net (code "37") (name "/DQ10") (class "Default")
      (node (ref "U1") (pin "D4") (pinfunction "IO_L11N_T1_SRCC_35_D4") (pintype "bidirectional"))
    )
    (net (code "38") (name "/DQ11") (class "Default")
      (node (ref "U1") (pin "A3") (pinfunction "IO_L8N_T1_AD14N_35_A3") (pintype "bidirectional"))
    )
    (net (code "39") (name "/DQ12") (class "Default")
      (node (ref "U1") (pin "E3") (pinfunction "IO_L12P_T1_MRCC_35_E3") (pintype "bidirectional"))
    )
    (net (code "40") (name "/DQ13") (class "Default")
      (node (ref "U1") (pin "A4") (pinfunction "IO_L8P_T1_AD14P_35_A4") (pintype "bidirectional"))
    )
    (net (code "41") (name "/DQ14") (class "Default")
      (node (ref "U1") (pin "C4") (pinfunction "IO_L7P_T1_AD6P_35_C4") (pintype "bidirectional"))
    )
    (net (code "42") (name "/DQ15") (class "Default")
      (node (ref "U1") (pin "B4") (pinfunction "IO_L7N_T1_AD6N_35_B4") (pintype "bidirectional"))
    )
    (net (code "43") (name "/GCLK") (class "Default")
      (node (ref "R9") (pin "2") (pintype "passive"))
      (node (ref "U1") (pin "T14") (pinfunction "IO_L14P_T2_SRCC_14_T14") (pintype "bidirectional"))
    )
    (net (code "44") (name "/LDM") (class "Default")
      (node (ref "U1") (pin "C7") (pinfunction "IO_L4N_T0_35_C7") (pintype "bidirectional"))
    )
    (net (code "45") (name "/LD_N") (class "Default")
      (node (ref "U1") (pin "A5") (pinfunction "IO_L3N_T0_DQS_AD5N_35_A5") (pintype "bidirectional"))
    )
    (net (code "46") (name "/LD_P") (class "Default")
      (node (ref "U1") (pin "A6") (pinfunction "IO_L3P_T0_DQS_AD5P_35_A6") (pintype "bidirectional"))
    )
    (net (code "47") (name "/LED1") (class "Default")
      (node (ref "R1") (pin "2") (pintype "passive"))
      (node (ref "U1") (pin "D10") (pinfunction "IO_L19N_T3_VREF_16_D10") (pintype "bidirectional"))
    )
    (net (code "48") (name "/LED2") (class "Default")
      (node (ref "R3") (pin "2") (pintype "passive"))
      (node (ref "U1") (pin "C11") (pinfunction "IO_L13P_T2_MRCC_16_C11") (pintype "bidirectional"))
    )
    (net (code "49") (name "/LED3") (class "Default")
      (node (ref "R4") (pin "2") (pintype "passive"))
      (node (ref "U1") (pin "C10") (pinfunction "IO_L13N_T2_MRCC_16_C10") (pintype "bidirectional"))
    )
    (net (code "50") (name "/LED4") (class "Default")
      (node (ref "R7") (pin "2") (pintype "passive"))
      (node (ref "U1") (pin "B8") (pinfunction "IO_L12P_T1_MRCC_16_B8") (pintype "bidirectional"))
    )
    (net (code "51") (name "/MA0") (class "Default")
      (node (ref "U1") (pin "E1") (pinfunction "IO_L18N_T2_35_E1") (pintype "bidirectional"))
    )
    (net (code "52") (name "/MA1") (class "Default")
      (node (ref "U1") (pin "F1") (pinfunction "IO_L18P_T2_35_F1") (pintype "bidirectional"))
    )
    (net (code "53") (name "/MA2") (class "Default")
      (node (ref "U1") (pin "E2") (pinfunction "IO_L14P_T2_SRCC_35_E2") (pintype "bidirectional"))
    )
    (net (code "54") (name "/MA3") (class "Default")
      (node (ref "U1") (pin "C1") (pinfunction "IO_L16N_T2_35_C1") (pintype "bidirectional"))
    )
    (net (code "55") (name "/MA4") (class "Default")
      (node (ref "U1") (pin "H2") (pinfunction "IO_L15P_T2_DQS_35_H2") (pintype "bidirectional"))
    )
    (net (code "56") (name "/MA5") (class "Default")
      (node (ref "U1") (pin "C2") (pinfunction "IO_L16P_T2_35_C2") (pintype "bidirectional"))
    )
    (net (code "57") (name "/MA6") (class "Default")
      (node (ref "U1") (pin "J5") (pinfunction "IO_25_35_J5") (pintype "bidirectional"))
    )
    (net (code "58") (name "/MA7") (class "Default")
      (node (ref "U1") (pin "H1") (pinfunction "IO_L17P_T2_35_H1") (pintype "bidirectional"))
    )
    (net (code "59") (name "/MA8") (class "Default")
      (node (ref "U1") (pin "G6") (pinfunction "IO_L19P_T3_35_G6") (pintype "bidirectional"))
    )
    (net (code "60") (name "/MA9") (class "Default")
      (node (ref "U1") (pin "F3") (pinfunction "IO_L13N_T2_MRCC_35_F3") (pintype "bidirectional"))
    )
    (net (code "61") (name "/MA10") (class "Default")
      (node (ref "U1") (pin "G1") (pinfunction "IO_L17N_T2_35_G1") (pintype "bidirectional"))
    )
    (net (code "62") (name "/MA11") (class "Default")
      (node (ref "U1") (pin "H5") (pinfunction "IO_L24N_T3_35_H5") (pintype "bidirectional"))
    )
    (net (code "63") (name "/MA12") (class "Default")
      (node (ref "U1") (pin "G2") (pinfunction "IO_L15N_T2_DQS_35_G2") (pintype "bidirectional"))
    )
    (net (code "64") (name "/MA13") (class "Default")
      (node (ref "U1") (pin "F4") (pinfunction "IO_L13P_T2_MRCC_35_F4") (pintype "bidirectional"))
    )
    (net (code "65") (name "/MA14") (class "Default")
      (node (ref "U1") (pin "F6") (pinfunction "IO_L19N_T3_VREF_35_F6") (pintype "bidirectional"))
    )
    (net (code "66") (name "/MA15") (class "Default")
      (node (ref "U1") (pin "D3") (pinfunction "IO_L12N_T1_MRCC_35_D3") (pintype "bidirectional"))
    )
    (net (code "67") (name "/MC32") (class "Default")
      (node (ref "U1") (pin "V11") (pinfunction "IO_L21N_T3_DQS_A06_D22_14_V11") (pintype "bidirectional"))
    )
    (net (code "68") (name "/MC33") (class "Default")
      (node (ref "U1") (pin "V12") (pinfunction "IO_L20N_T3_A07_D23_14_V12") (pintype "bidirectional"))
    )
    (net (code "69") (name "/MC34") (class "Default")
      (node (ref "U1") (pin "U11") (pinfunction "IO_L19N_T3_A09_D25_VREF_14_U11") (pintype "bidirectional"))
    )
    (net (code "70") (name "/MC35") (class "Default")
      (node (ref "U1") (pin "U12") (pinfunction "IO_L20P_T3_A08_D24_14_U12") (pintype "bidirectional"))
    )
    (net (code "71") (name "/MC36") (class "Default")
      (node (ref "U1") (pin "T10") (pinfunction "IO_L24N_T3_A00_D16_14_T10") (pintype "bidirectional"))
    )
    (net (code "72") (name "/MC37") (class "Default")
      (node (ref "U1") (pin "T9") (pinfunction "IO_L24P_T3_A01_D17_14_T9") (pintype "bidirectional"))
    )
    (net (code "73") (name "/MC38") (class "Default")
      (node (ref "U1") (pin "T11") (pinfunction "IO_L19P_T3_A10_D26_14_T11") (pintype "bidirectional"))
    )
    (net (code "74") (name "/MC39") (class "Default")
      (node (ref "U1") (pin "R10") (pinfunction "IO_25_14_R10") (pintype "bidirectional"))
    )
    (net (code "75") (name "/MCEN") (class "Default")
      (node (ref "U1") (pin "V10") (pinfunction "IO_L21P_T3_DQS_14_V10") (pintype "bidirectional"))
    )
    (net (code "76") (name "/ODT") (class "Default")
      (node (ref "U1") (pin "H6") (pinfunction "IO_L24P_T3_35_H6") (pintype "bidirectional"))
    )
    (net (code "77") (name "/P14*") (class "Default")
      (node (ref "PIN14") (pin "14") (pintype "passive"))
      (node (ref "U1") (pin "A8") (pinfunction "IO_L12N_T1_MRCC_16_A8") (pintype "bidirectional"))
    )
    (net (code "78") (name "/P15*") (class "Default")
      (node (ref "PIN15") (pin "15") (pintype "passive"))
      (node (ref "U1") (pin "A9") (pinfunction "IO_L14N_T2_SRCC_16_A9") (pintype "bidirectional"))
    )
    (net (code "79") (name "/P16*") (class "Default")
      (node (ref "PIN16") (pin "16") (pintype "passive"))
      (node (ref "U1") (pin "A10") (pinfunction "IO_L14P_T2_SRCC_16_A10") (pintype "bidirectional"))
    )
    (net (code "80") (name "/P17*") (class "Default")
      (node (ref "PIN17") (pin "17") (pintype "passive"))
      (node (ref "U1") (pin "D15") (pinfunction "IO_L12P_T1_MRCC_15_D15") (pintype "bidirectional"))
    )
    (net (code "81") (name "/P18*") (class "Default")
      (node (ref "PIN18") (pin "18") (pintype "passive"))
      (node (ref "U1") (pin "A11") (pinfunction "IO_L4N_T0_15_A11") (pintype "bidirectional"))
    )
    (net (code "82") (name "/P19*") (class "Default")
      (node (ref "PIN19") (pin "19") (pintype "passive"))
      (node (ref "U1") (pin "B11") (pinfunction "IO_L4P_T0_15_B11") (pintype "bidirectional"))
    )
    (net (code "83") (name "/P20") (class "Default")
      (node (ref "PIN20") (pin "20") (pintype "passive"))
      (node (ref "U1") (pin "K6") (pinfunction "IO_0_34_K6") (pintype "bidirectional"))
    )
    (net (code "84") (name "/P21*") (class "Default")
      (node (ref "PIN21") (pin "21") (pintype "passive"))
      (node (ref "U1") (pin "D12") (pinfunction "IO_L6P_T0_15_D12") (pintype "bidirectional"))
    )
    (net (code "85") (name "/P22*") (class "Default")
      (node (ref "PIN22") (pin "22") (pintype "passive"))
      (node (ref "U1") (pin "C12") (pinfunction "IO_L3P_T0_DQS_AD1P_15_C12") (pintype "bidirectional"))
    )
    (net (code "86") (name "/P23*") (class "Default")
      (node (ref "PIN23") (pin "23") (pintype "passive"))
      (node (ref "U1") (pin "B12") (pinfunction "IO_L3N_T0_DQS_AD1N_15_B12") (pintype "bidirectional"))
    )
    (net (code "87") (name "/P24") (class "Default")
      (node (ref "PIN24") (pin "24") (pintype "passive"))
      (node (ref "U1") (pin "K5") (pinfunction "IO_L5P_T0_34_K5") (pintype "bidirectional"))
    )
    (net (code "88") (name "/P25*") (class "Default")
      (node (ref "PIN25") (pin "25") (pintype "passive"))
      (node (ref "U1") (pin "F13") (pinfunction "IO_L5P_T0_AD9P_15_F13") (pintype "bidirectional"))
    )
    (net (code "89") (name "/P26*") (class "Default")
      (node (ref "PIN26") (pin "26") (pintype "passive"))
      (node (ref "U1") (pin "J13") (pinfunction "IO_L17N_T2_A25_15_J13") (pintype "bidirectional"))
    )
    (net (code "90") (name "/P27*") (class "Default")
      (node (ref "PIN27") (pin "27") (pintype "passive"))
      (node (ref "U1") (pin "K13") (pinfunction "IO_L17P_T2_A26_15_K13") (pintype "bidirectional"))
    )
    (net (code "91") (name "/P28") (class "Default")
      (node (ref "PIN28") (pin "28") (pintype "passive"))
      (node (ref "U1") (pin "K3") (pinfunction "IO_L2P_T0_34_K3") (pintype "bidirectional"))
    )
    (net (code "92") (name "/P29") (class "Default")
      (node (ref "PIN29") (pin "29") (pintype "passive"))
      (node (ref "U1") (pin "L1") (pinfunction "IO_L1P_T0_34_L1") (pintype "bidirectional"))
    )
    (net (code "93") (name "/P30") (class "Default")
      (node (ref "PIN30") (pin "30") (pintype "passive"))
      (node (ref "U1") (pin "L3") (pinfunction "IO_L2N_T0_34_L3") (pintype "bidirectional"))
    )
    (net (code "94") (name "/P31") (class "Default")
      (node (ref "PIN31") (pin "31") (pintype "passive"))
      (node (ref "U1") (pin "V1") (pinfunction "IO_L7N_T1_34_V1") (pintype "bidirectional"))
    )
    (net (code "95") (name "/P32*") (class "Default")
      (node (ref "PIN32") (pin "32") (pintype "passive"))
      (node (ref "U1") (pin "L14") (pinfunction "IO_L2P_T0_D02_14_L14") (pintype "bidirectional"))
    )
    (net (code "96") (name "/P33*") (class "Default")
      (node (ref "PIN33") (pin "33") (pintype "passive"))
      (node (ref "U1") (pin "M13") (pinfunction "IO_L6N_T0_D08_VREF_14_M13") (pintype "bidirectional"))
    )
    (net (code "97") (name "/P34*") (class "Default")
      (node (ref "PIN34") (pin "34") (pintype "passive"))
      (node (ref "U1") (pin "M14") (pinfunction "IO_L2N_T0_D03_14_M14") (pintype "bidirectional"))
    )
    (net (code "98") (name "/P35*") (class "Default")
      (node (ref "PIN35") (pin "35") (pintype "passive"))
      (node (ref "U1") (pin "N14") (pinfunction "IO_L8P_T1_D11_14_N14") (pintype "bidirectional"))
    )
    (net (code "99") (name "/P36*") (class "Default")
      (node (ref "PIN36") (pin "36") (pintype "passive"))
      (node (ref "U1") (pin "N15") (pinfunction "IO_L11P_T1_SRCC_14_N15") (pintype "bidirectional"))
    )
    (net (code "100") (name "/P37*") (class "Default")
      (node (ref "PIN37") (pin "37") (pintype "passive"))
      (node (ref "U1") (pin "P15") (pinfunction "IO_L13P_T2_MRCC_14_P15") (pintype "bidirectional"))
    )
    (net (code "101") (name "/P38*") (class "Default")
      (node (ref "PIN38") (pin "38") (pintype "passive"))
      (node (ref "U1") (pin "P14") (pinfunction "IO_L8N_T1_D12_14_P14") (pintype "bidirectional"))
    )
    (net (code "102") (name "/P39*") (class "Default")
      (node (ref "PIN39") (pin "39") (pintype "passive"))
      (node (ref "U1") (pin "R13") (pinfunction "IO_L5N_T0_D07_14_R13") (pintype "bidirectional"))
    )
    (net (code "103") (name "/P40") (class "Default")
      (node (ref "PIN40") (pin "40") (pintype "passive"))
      (node (ref "U1") (pin "U1") (pinfunction "IO_L7P_T1_34_U1") (pintype "bidirectional"))
    )
    (net (code "104") (name "/P41") (class "Default")
      (node (ref "PIN41") (pin "41") (pintype "passive"))
      (node (ref "U1") (pin "U2") (pinfunction "IO_L9P_T1_DQS_34_U2") (pintype "bidirectional"))
    )
    (net (code "105") (name "/P42") (class "Default")
      (node (ref "PIN42") (pin "42") (pintype "passive"))
      (node (ref "U1") (pin "V2") (pinfunction "IO_L9N_T1_DQS_34_V2") (pintype "bidirectional"))
    )
    (net (code "106") (name "/P43") (class "Default")
      (node (ref "PIN43") (pin "43") (pintype "passive"))
      (node (ref "U1") (pin "T3") (pinfunction "IO_L11N_T1_SRCC_34_T3") (pintype "bidirectional"))
    )
    (net (code "107") (name "/P44") (class "Default")
      (node (ref "PIN44") (pin "44") (pintype "passive"))
      (node (ref "U1") (pin "U3") (pinfunction "IO_L8N_T1_34_U3") (pintype "bidirectional"))
    )
    (net (code "108") (name "/P45") (class "Default")
      (node (ref "PIN45") (pin "45") (pintype "passive"))
      (node (ref "U1") (pin "V4") (pinfunction "IO_L10N_T1_34_V4") (pintype "bidirectional"))
    )
    (net (code "109") (name "/P46") (class "Default")
      (node (ref "PIN46") (pin "46") (pintype "passive"))
      (node (ref "U1") (pin "V6") (pinfunction "IO_L20N_T3_34_V6") (pintype "bidirectional"))
    )
    (net (code "110") (name "/P47") (class "Default")
      (node (ref "PIN47") (pin "47") (pintype "passive"))
      (node (ref "U1") (pin "V7") (pinfunction "IO_L20P_T3_34_V7") (pintype "bidirectional"))
    )
    (net (code "111") (name "/P48") (class "Default")
      (node (ref "PIN48") (pin "48") (pintype "passive"))
      (node (ref "U1") (pin "V9") (pinfunction "IO_L21N_T3_DQS_34_V9") (pintype "bidirectional"))
    )
    (net (code "112") (name "/P49") (class "Default")
      (node (ref "PIN49") (pin "49") (pintype "passive"))
      (node (ref "U1") (pin "U9") (pinfunction "IO_L21P_T3_DQS_34_U9") (pintype "bidirectional"))
    )
    (net (code "113") (name "/P50") (class "Default")
      (node (ref "PIN50") (pin "50") (pintype "passive"))
      (node (ref "U1") (pin "U6") (pinfunction "IO_L22N_T3_34_U6") (pintype "bidirectional"))
    )
    (net (code "114") (name "/P51") (class "Default")
      (node (ref "PIN51") (pin "51") (pintype "passive"))
      (node (ref "U1") (pin "U7") (pinfunction "IO_L22P_T3_34_U7") (pintype "bidirectional"))
    )
    (net (code "115") (name "/P52") (class "Default")
      (node (ref "PIN52") (pin "52") (pintype "passive"))
      (node (ref "U1") (pin "U8") (pinfunction "IO_25_34_U8") (pintype "bidirectional"))
    )
    (net (code "116") (name "/P53") (class "Default")
      (node (ref "PIN53") (pin "53") (pintype "passive"))
      (node (ref "U1") (pin "T8") (pinfunction "IO_L24N_T3_34_T8") (pintype "bidirectional"))
    )
    (net (code "117") (name "/P54") (class "Default")
      (node (ref "PIN54") (pin "54") (pintype "passive"))
      (node (ref "U1") (pin "R7") (pinfunction "IO_L23P_T3_34_R7") (pintype "bidirectional"))
    )
    (net (code "118") (name "/P55") (class "Default")
      (node (ref "PIN55") (pin "55") (pintype "passive"))
      (node (ref "U1") (pin "R8") (pinfunction "IO_L24P_T3_34_R8") (pintype "bidirectional"))
    )
    (net (code "119") (name "/P56") (class "Default")
      (node (ref "PIN56") (pin "56") (pintype "passive"))
      (node (ref "U1") (pin "P5") (pinfunction "IO_L13N_T2_MRCC_34_P5") (pintype "bidirectional"))
    )
    (net (code "120") (name "/P57") (class "Default")
      (node (ref "PIN57") (pin "57") (pintype "passive"))
      (node (ref "U1") (pin "N5") (pinfunction "IO_L13P_T2_MRCC_34_N5") (pintype "bidirectional"))
    )
    (net (code "121") (name "/P58") (class "Default")
      (node (ref "PIN58") (pin "58") (pintype "passive"))
      (node (ref "U1") (pin "N6") (pinfunction "IO_L18N_T2_34_N6") (pintype "bidirectional"))
    )
    (net (code "122") (name "/P59") (class "Default")
      (node (ref "PIN59") (pin "59") (pintype "passive"))
      (node (ref "U1") (pin "M6") (pinfunction "IO_L18P_T2_34_M6") (pintype "bidirectional"))
    )
    (net (code "123") (name "/P60*") (class "Default")
      (node (ref "PIN60") (pin "60") (pintype "passive"))
      (node (ref "U1") (pin "K16") (pinfunction "IO_25_15_K16") (pintype "bidirectional"))
    )
    (net (code "124") (name "/P61*") (class "Default")
      (node (ref "PIN61") (pin "61") (pintype "passive"))
      (node (ref "U1") (pin "G18") (pinfunction "IO_L22P_T3_A17_15_G18") (pintype "bidirectional"))
    )
    (net (code "125") (name "/P62*") (class "Default")
      (node (ref "PIN62") (pin "62") (pintype "passive"))
      (node (ref "U1") (pin "F18") (pinfunction "IO_L22N_T3_A16_15_F18") (pintype "bidirectional"))
    )
    (net (code "126") (name "/P63*") (class "Default")
      (node (ref "PIN63") (pin "63") (pintype "passive"))
      (node (ref "U1") (pin "E18") (pinfunction "IO_L21P_T3_DQS_15_E18") (pintype "bidirectional"))
    )
    (net (code "127") (name "/P64*") (class "Default")
      (node (ref "PIN64") (pin "64") (pintype "passive"))
      (node (ref "U1") (pin "J14") (pinfunction "IO_L19P_T3_A22_15_J14") (pintype "bidirectional"))
    )
    (net (code "128") (name "/P65*") (class "Default")
      (node (ref "PIN65") (pin "65") (pintype "passive"))
      (node (ref "U1") (pin "J17") (pinfunction "IO_L23P_T3_FOE_B_15_J17") (pintype "bidirectional"))
    )
    (net (code "129") (name "/P66*") (class "Default")
      (node (ref "PIN66") (pin "66") (pintype "passive"))
      (node (ref "U1") (pin "H17") (pinfunction "IO_L18P_T2_A24_15_H17") (pintype "bidirectional"))
    )
    (net (code "130") (name "/P67*") (class "Default")
      (node (ref "PIN67") (pin "67") (pintype "passive"))
      (node (ref "U1") (pin "G17") (pinfunction "IO_L18N_T2_A23_15_G17") (pintype "bidirectional"))
    )
    (net (code "131") (name "/P68*") (class "Default")
      (node (ref "PIN68") (pin "68") (pintype "passive"))
      (node (ref "U1") (pin "H16") (pinfunction "IO_L13P_T2_MRCC_15_H16") (pintype "bidirectional"))
    )
    (net (code "132") (name "/P69*") (class "Default")
      (node (ref "PIN69") (pin "69") (pintype "passive"))
      (node (ref "U1") (pin "H15") (pinfunction "IO_L19N_T3_A21_VREF_15_H15") (pintype "bidirectional"))
    )
    (net (code "133") (name "/P70*") (class "Default")
      (node (ref "PIN70") (pin "70") (pintype "passive"))
      (node (ref "U1") (pin "E17") (pinfunction "IO_L16P_T2_A28_15_E17") (pintype "bidirectional"))
    )
    (net (code "134") (name "/P71*") (class "Default")
      (node (ref "PIN71") (pin "71") (pintype "passive"))
      (node (ref "U1") (pin "J15") (pinfunction "IO_L24N_T3_RS0_15_J15") (pintype "bidirectional"))
    )
    (net (code "135") (name "/P72*") (class "Default")
      (node (ref "PIN72") (pin "72") (pintype "passive"))
      (node (ref "U1") (pin "G16") (pinfunction "IO_L13N_T2_MRCC_15_G16") (pintype "bidirectional"))
    )
    (net (code "136") (name "/P73*") (class "Default")
      (node (ref "PIN73") (pin "73") (pintype "passive"))
      (node (ref "U1") (pin "F16") (pinfunction "IO_L14N_T2_SRCC_15_F16") (pintype "bidirectional"))
    )
    (net (code "137") (name "/P74") (class "Default")
      (node (ref "PIN74") (pin "74") (pintype "passive"))
      (node (ref "U1") (pin "L6") (pinfunction "IO_L6P_T0_34_L6") (pintype "bidirectional"))
    )
    (net (code "138") (name "/PPON") (class "Default") (node (ref "PIN3") (pin "3") (pintype "passive")))
    (net (code "139") (name "/PWRON") (class "Default") (node (ref "PIN7") (pin "7") (pintype "passive")))
    (net (code "140") (name "/RAS#") (class "Default")
      (node (ref "U1") (pin "D2") (pinfunction "IO_L14N_T2_SRCC_35_D2") (pintype "bidirectional"))
    )
    (net (code "141") (name "/RST#") (class "Default")
      (node (ref "U1") (pin "F5") (pinfunction "IO_0_35_F5") (pintype "bidirectional"))
    )
    (net (code "142") (name "/TCK") (class "Default")
      (node (ref "PIN82") (pin "82") (pintype "passive"))
      (node (ref "U1") (pin "E10") (pinfunction "TCK_0_E10") (pintype "input"))
    )
    (net (code "143") (name "/TDI") (class "Default")
      (node (ref "PIN83") (pin "83") (pintype "passive"))
      (node (ref "U1") (pin "E11") (pinfunction "TDI_0_E11") (pintype "input"))
    )
    (net (code "144") (name "/TDO") (class "Default")
      (node (ref "PIN81") (pin "81") (pintype "passive"))
      (node (ref "U1") (pin "E13") (pinfunction "TDO_0_E13") (pintype "output"))
    )
    (net (code "145") (name "/TMS") (class "Default")
      (node (ref "PIN80") (pin "80") (pintype "passive"))
      (node (ref "U1") (pin "E12") (pinfunction "TMS_0_E12") (pintype "input"))
    )
    (net (code "146") (name "/UDM") (class "Default")
      (node (ref "U1") (pin "B2") (pinfunction "IO_L10N_T1_AD15N_35_B2") (pintype "bidirectional"))
    )
    (net (code "147") (name "/UD_N") (class "Default")
      (node (ref "U1") (pin "A1") (pinfunction "IO_L9N_T1_DQS_AD7N_35_A1") (pintype "bidirectional"))
    )
    (net (code "148") (name "/UD_P") (class "Default")
      (node (ref "U1") (pin "B1") (pinfunction "IO_L9P_T1_DQS_AD7P_35_B1") (pintype "bidirectional"))
    )
    (net (code "149") (name "/USBID") (class "Default") (node (ref "PIN76") (pin "76") (pintype "passive")))
    (net (code "150") (name "/USB_CLK") (class "Default")
      (node (ref "U1") (pin "C14") (pinfunction "IO_L1N_T0_AD0N_15_C14") (pintype "bidirectional"))
    )
    (net (code "151") (name "/USB_D0") (class "Default")
      (node (ref "U1") (pin "A18") (pinfunction "IO_L10N_T1_AD11N_15_A18") (pintype "bidirectional"))
    )
    (net (code "152") (name "/USB_D1") (class "Default")
      (node (ref "U1") (pin "B18") (pinfunction "IO_L10P_T1_AD11P_15_B18") (pintype "bidirectional"))
    )
    (net (code "153") (name "/USB_D2") (class "Default")
      (node (ref "U1") (pin "D18") (pinfunction "IO_L21N_T3_DQS_A18_15_D18") (pintype "bidirectional"))
    )
    (net (code "154") (name "/USB_D3") (class "Default")
      (node (ref "U1") (pin "C17") (pinfunction "IO_L20N_T3_A19_15_C17") (pintype "bidirectional"))
    )
    (net (code "155") (name "/USB_D4") (class "Default")
      (node (ref "U1") (pin "D17") (pinfunction "IO_L16N_T2_A27_15_D17") (pintype "bidirectional"))
    )
    (net (code "156") (name "/USB_D5") (class "Default")
      (node (ref "U1") (pin "C16") (pinfunction "IO_L20P_T3_A20_15_C16") (pintype "bidirectional"))
    )
    (net (code "157") (name "/USB_D6") (class "Default")
      (node (ref "U1") (pin "E16") (pinfunction "IO_L11N_T1_SRCC_15_E16") (pintype "bidirectional"))
    )
    (net (code "158") (name "/USB_D7") (class "Default")
      (node (ref "U1") (pin "E15") (pinfunction "IO_L11P_T1_SRCC_15_E15") (pintype "bidirectional"))
    )
    (net (code "159") (name "/USB_DIR") (class "Default")
      (node (ref "U1") (pin "D14") (pinfunction "IO_L1P_T0_AD0P_15_D14") (pintype "bidirectional"))
    )
    (net (code "160") (name "/USB_NXT") (class "Default")
      (node (ref "U1") (pin "D13") (pinfunction "IO_L6N_T0_VREF_15_D13") (pintype "bidirectional"))
    )
    (net (code "161") (name "/USB_STP") (class "Default")
      (node (ref "U1") (pin "B13") (pinfunction "IO_L2P_T0_AD8P_15_B13") (pintype "bidirectional"))
    )
    (net (code "162") (name "/VBUS") (class "Default") (node (ref "PIN75") (pin "75") (pintype "passive")))
    (net (code "163") (name "/WE#") (class "Default")
      (node (ref "U1") (pin "K1") (pinfunction "IO_L23N_T3_35_K1") (pintype "bidirectional"))
    )
    (net (code "164") (name "/eCLK") (class "Default")
      (node (ref "U1") (pin "G13") (pinfunction "IO_0_15_G13") (pintype "bidirectional"))
    )
    (net (code "165") (name "/eCMD") (class "Default")
      (node (ref "U1") (pin "G14") (pinfunction "IO_L15N_T2_DQS_ADV_B_15_G14") (pintype "bidirectional"))
    )
    (net (code "166") (name "/eDAT0") (class "Default")
      (node (ref "U1") (pin "B17") (pinfunction "IO_L7N_T1_AD2N_15_B17") (pintype "bidirectional"))
    )
    (net (code "167") (name "/eDAT1") (class "Default")
      (node (ref "U1") (pin "C15") (pinfunction "IO_L12N_T1_MRCC_15_C15") (pintype "bidirectional"))
    )
    (net (code "168") (name "/eDAT2") (class "Default")
      (node (ref "U1") (pin "B14") (pinfunction "IO_L2N_T0_AD8N_15_B14") (pintype "bidirectional"))
    )
    (net (code "169") (name "/eDAT3") (class "Default")
      (node (ref "U1") (pin "A16") (pinfunction "IO_L8N_T1_AD10N_15_A16") (pintype "bidirectional"))
    )
    (net (code "170") (name "/eDAT4") (class "Default")
      (node (ref "U1") (pin "B16") (pinfunction "IO_L7P_T1_AD2P_15_B16") (pintype "bidirectional"))
    )
    (net (code "171") (name "/eDAT5") (class "Default")
      (node (ref "U1") (pin "A15") (pinfunction "IO_L8P_T1_AD10P_15_A15") (pintype "bidirectional"))
    )
    (net (code "172") (name "/eDAT6") (class "Default")
      (node (ref "U1") (pin "A14") (pinfunction "IO_L9N_T1_DQS_AD3N_15_A14") (pintype "bidirectional"))
    )
    (net (code "173") (name "/eDAT7") (class "Default")
      (node (ref "U1") (pin "A13") (pinfunction "IO_L9P_T1_DQS_AD3P_15_A13") (pintype "bidirectional"))
    )
    (net (code "174") (name "/eRST#") (class "Default")
      (node (ref "U1") (pin "F14") (pinfunction "IO_L5N_T0_AD9N_15_F14") (pintype "bidirectional"))
    )
    (net (code "175") (name "/nDONE") (class "Default")
      (node (ref "PIN79") (pin "79") (pintype "passive"))
      (node (ref "R6") (pin "2") (pintype "passive"))
      (node (ref "U1") (pin "P10") (pinfunction "DONE_0_P10") (pintype "bidirectional"))
    )
    (net (code "176") (name "/nINIT") (class "Default")
      (node (ref "PIN1") (pin "1") (pintype "passive"))
      (node (ref "R5") (pin "1") (pintype "passive"))
      (node (ref "U1") (pin "P7") (pinfunction "INIT_B_0_P7") (pintype "bidirectional"))
    )
    (net (code "177") (name "/nRESET") (class "Default")
      (node (ref "PIN84") (pin "84") (pintype "passive"))
      (node (ref "R2") (pin "1") (pintype "passive"))
      (node (ref "U1") (pin "P9") (pinfunction "PROGRAM_B_0_P9") (pintype "input"))
    )
    (net (code "178") (name "GND") (class "Default")
      (node (ref "C1") (pin "2") (pintype "passive"))
      (node (ref "C10") (pin "1") (pintype "passive"))
      (node (ref "C11") (pin "2") (pintype "passive"))
      (node (ref "C12") (pin "1") (pintype "passive"))
      (node (ref "C13") (pin "2") (pintype "passive"))
      (node (ref "C14") (pin "1") (pintype "passive"))
      (node (ref "C15") (pin "2") (pintype "passive"))
      (node (ref "C16") (pin "1") (pintype "passive"))
      (node (ref "C17") (pin "2") (pintype "passive"))
      (node (ref "C18") (pin "1") (pintype "passive"))
      (node (ref "C19") (pin "2") (pintype "passive"))
      (node (ref "C2") (pin "1") (pintype "passive"))
      (node (ref "C20") (pin "1") (pintype "passive"))
      (node (ref "C21") (pin "2") (pintype "passive"))
      (node (ref "C22") (pin "1") (pintype "passive"))
      (node (ref "C23") (pin "2") (pintype "passive"))
      (node (ref "C24") (pin "1") (pintype "passive"))
      (node (ref "C25") (pin "2") (pintype "passive"))
      (node (ref "C26") (pin "1") (pintype "passive"))
      (node (ref "C27") (pin "2") (pintype "passive"))
      (node (ref "C28") (pin "1") (pintype "passive"))
      (node (ref "C29") (pin "2") (pintype "passive"))
      (node (ref "C3") (pin "2") (pintype "passive"))
      (node (ref "C30") (pin "1") (pintype "passive"))
      (node (ref "C31") (pin "2") (pintype "passive"))
      (node (ref "C32") (pin "2") (pintype "passive"))
      (node (ref "C33") (pin "2") (pintype "passive"))
      (node (ref "C34") (pin "2") (pintype "passive"))
      (node (ref "C35") (pin "1") (pintype "passive"))
      (node (ref "C36") (pin "2") (pintype "passive"))
      (node (ref "C37") (pin "2") (pintype "passive"))
      (node (ref "C38") (pin "1") (pintype "passive"))
      (node (ref "C39") (pin "2") (pintype "passive"))
      (node (ref "C4") (pin "1") (pintype "passive"))
      (node (ref "C40") (pin "1") (pintype "passive"))
      (node (ref "C41") (pin "1") (pintype "passive"))
      (node (ref "C42") (pin "2") (pintype "passive"))
      (node (ref "C43") (pin "1") (pintype "passive"))
      (node (ref "C44") (pin "2") (pintype "passive"))
      (node (ref "C45") (pin "1") (pintype "passive"))
      (node (ref "C46") (pin "2") (pintype "passive"))
      (node (ref "C47") (pin "2") (pintype "passive"))
      (node (ref "C48") (pin "2") (pintype "passive"))
      (node (ref "C49") (pin "1") (pintype "passive"))
      (node (ref "C5") (pin "2") (pintype "passive"))
      (node (ref "C50") (pin "2") (pintype "passive"))
      (node (ref "C51") (pin "1") (pintype "passive"))
      (node (ref "C6") (pin "1") (pintype "passive"))
      (node (ref "C7") (pin "2") (pintype "passive"))
      (node (ref "C8") (pin "1") (pintype "passive"))
      (node (ref "C9") (pin "2") (pintype "passive"))
      (node (ref "L1") (pin "2") (pintype "passive"))
      (node (ref "LED1") (pin "1") (pintype "passive"))
      (node (ref "LED2") (pin "1") (pintype "passive"))
      (node (ref "LED3") (pin "1") (pintype "passive"))
      (node (ref "LED4") (pin "1") (pintype "passive"))
      (node (ref "PIN10") (pin "10") (pintype "passive"))
      (node (ref "PIN11") (pin "11") (pintype "passive"))
      (node (ref "U1") (pin "A12") (pinfunction "GND_A12") (pintype "power_in"))
      (node (ref "U1") (pin "A2") (pinfunction "GND_A2") (pintype "power_in"))
      (node (ref "U1") (pin "B15") (pinfunction "GND_B15") (pintype "power_in"))
      (node (ref "U1") (pin "B5") (pinfunction "GND_B5") (pintype "power_in"))
      (node (ref "U1") (pin "C18") (pinfunction "GND_C18") (pintype "power_in"))
      (node (ref "U1") (pin "C8") (pinfunction "GND_C8") (pintype "power_in"))
      (node (ref "U1") (pin "D1") (pinfunction "GND_D1") (pintype "power_in"))
      (node (ref "U1") (pin "D11") (pinfunction "GND_D11") (pintype "power_in"))
      (node (ref "U1") (pin "E14") (pinfunction "GND_E14") (pintype "power_in"))
      (node (ref "U1") (pin "E4") (pinfunction "GND_E4") (pintype "power_in"))
      (node (ref "U1") (pin "F11") (pinfunction "GND_F11") (pintype "power_in"))
      (node (ref "U1") (pin "F17") (pinfunction "GND_F17") (pintype "power_in"))
      (node (ref "U1") (pin "F7") (pinfunction "GND_F7") (pintype "power_in"))
      (node (ref "U1") (pin "F9") (pinfunction "GND_F9") (pintype "power_in"))
      (node (ref "U1") (pin "G10") (pinfunction "GND_G10") (pintype "power_in"))
      (node (ref "U1") (pin "G12") (pinfunction "GND_G12") (pintype "power_in"))
      (node (ref "U1") (pin "G8") (pinfunction "GND_G8") (pintype "power_in"))
      (node (ref "U1") (pin "H11") (pinfunction "GND_H11") (pintype "power_in"))
      (node (ref "U1") (pin "H13") (pinfunction "GND_H13") (pintype "power_in"))
      (node (ref "U1") (pin "H3") (pinfunction "GND_H3") (pintype "power_in"))
      (node (ref "U1") (pin "H7") (pinfunction "GND_H7") (pintype "power_in"))
      (node (ref "U1") (pin "J12") (pinfunction "GND_J12") (pintype "power_in"))
      (node (ref "U1") (pin "J16") (pinfunction "GND_J16") (pintype "power_in"))
      (node (ref "U1") (pin "J6") (pinfunction "GND_J6") (pintype "power_in"))
      (node (ref "U1") (pin "J8") (pinfunction "GND_J8") (pintype "power_in"))
      (node (ref "U1") (pin "J9") (pinfunction "VREFN_0_J9") (pintype "input"))
      (node (ref "U1") (pin "K10") (pinfunction "VREFP_0_K10") (pintype "input"))
      (node (ref "U1") (pin "K11") (pinfunction "GND_K11") (pintype "power_in"))
      (node (ref "U1") (pin "K7") (pinfunction "GND_K7") (pintype "power_in"))
      (node (ref "U1") (pin "L10") (pinfunction "DXP_0_L10") (pintype "input"))
      (node (ref "U1") (pin "L12") (pinfunction "GND_L12") (pintype "power_in"))
      (node (ref "U1") (pin "L15") (pinfunction "IO_L3P_T0_DQS_PUDC_B_14_L15") (pintype "bidirectional"))
      (node (ref "U1") (pin "L2") (pinfunction "GND_L2") (pintype "power_in"))
      (node (ref "U1") (pin "L8") (pinfunction "GND_L8") (pintype "power_in"))
      (node (ref "U1") (pin "L9") (pinfunction "DXN_0_L9") (pintype "input"))
      (node (ref "U1") (pin "M11") (pinfunction "GND_M11") (pintype "power_in"))
      (node (ref "U1") (pin "M15") (pinfunction "GND_M15") (pintype "power_in"))
      (node (ref "U1") (pin "M5") (pinfunction "GND_M5") (pintype "power_in"))
      (node (ref "U1") (pin "M7") (pinfunction "GND_M7") (pintype "power_in"))
      (node (ref "U1") (pin "M9") (pinfunction "GND_M9") (pintype "power_in"))
      (node (ref "U1") (pin "N10") (pinfunction "GND_N10") (pintype "power_in"))
      (node (ref "U1") (pin "N12") (pinfunction "GND_N12") (pintype "power_in"))
      (node (ref "U1") (pin "N18") (pinfunction "GND_N18") (pintype "power_in"))
      (node (ref "U1") (pin "N8") (pinfunction "GND_N8") (pintype "power_in"))
      (node (ref "U1") (pin "P1") (pinfunction "GND_P1") (pintype "power_in"))
      (node (ref "U1") (pin "P11") (pinfunction "M2_0_P11") (pintype "input"))
      (node (ref "U1") (pin "P13") (pinfunction "M1_0_P13") (pintype "input"))
      (node (ref "U1") (pin "R14") (pinfunction "GND_R14") (pintype "power_in"))
      (node (ref "U1") (pin "R4") (pinfunction "GND_R4") (pintype "power_in"))
      (node (ref "U1") (pin "T17") (pinfunction "GND_T17") (pintype "power_in"))
      (node (ref "U1") (pin "T7") (pinfunction "GND_T7") (pintype "power_in"))
      (node (ref "U1") (pin "U10") (pinfunction "GND_U10") (pintype "power_in"))
      (node (ref "U1") (pin "V13") (pinfunction "GND_V13") (pintype "power_in"))
      (node (ref "U1") (pin "V3") (pinfunction "GND_V3") (pintype "power_in"))
      (node (ref "U2") (pin "4") (pinfunction "GND_4") (pintype "power_in"))
      (node (ref "U3") (pin "2") (pinfunction "GND_2") (pintype "passive"))
    )
    (net (code "179") (name "Net-(LED1-Pad2)") (class "Default")
      (node (ref "LED1") (pin "2") (pintype "passive"))
      (node (ref "R1") (pin "1") (pintype "passive"))
    )
    (net (code "180") (name "Net-(LED2-Pad2)") (class "Default")
      (node (ref "LED2") (pin "2") (pintype "passive"))
      (node (ref "R3") (pin "1") (pintype "passive"))
    )
    (net (code "181") (name "Net-(LED3-Pad2)") (class "Default")
      (node (ref "LED3") (pin "2") (pintype "passive"))
      (node (ref "R4") (pin "1") (pintype "passive"))
    )
    (net (code "182") (name "Net-(LED4-Pad2)") (class "Default")
      (node (ref "LED4") (pin "2") (pintype "passive"))
      (node (ref "R7") (pin "1") (pintype "passive"))
    )
    (net (code "183") (name "Net-(U1H-VCCADC_0)") (class "Default")
      (node (ref "C49") (pin "2") (pintype "passive"))
      (node (ref "C51") (pin "2") (pintype "passive"))
      (node (ref "L2") (pin "1") (pintype "passive"))
      (node (ref "U1") (pin "H10") (pinfunction "VCCADC_0_H10") (pintype "power_in"))
    )
    (net (code "184") (name "Net-(U1I-GNDADC_0)") (class "Default")
      (node (ref "L1") (pin "1") (pintype "passive"))
      (node (ref "U1") (pin "H9") (pinfunction "GNDADC_0_H9") (pintype "power_in"))
    )
    (net (code "185") (name "Net-(U3-CLK)") (class "Default")
      (node (ref "R9") (pin "1") (pintype "passive"))
      (node (ref "U3") (pin "3") (pinfunction "CLK_3") (pintype "passive"))
    )
    (net (code "186") (name "unconnected-(U1A-IO_0_14-PadR11)") (class "Default")
      (node (ref "U1") (pin "R11") (pinfunction "IO_0_14_R11") (pintype "bidirectional+no_connect"))
    )
    (net (code "187") (name "unconnected-(U1A-IO_L3N_T0_DQS_EMCCLK_14-PadL16)") (class "Default")
      (node (ref "U1") (pin "L16") (pinfunction "IO_L3N_T0_DQS_EMCCLK_14_L16") (pintype "bidirectional+no_connect"))
    )
    (net (code "188") (name "unconnected-(U1A-IO_L4N_T0_D05_14-PadM18)") (class "Default")
      (node (ref "U1") (pin "M18") (pinfunction "IO_L4N_T0_D05_14_M18") (pintype "bidirectional+no_connect"))
    )
    (net (code "189") (name "unconnected-(U1A-IO_L4P_T0_D04_14-PadL18)") (class "Default")
      (node (ref "U1") (pin "L18") (pinfunction "IO_L4P_T0_D04_14_L18") (pintype "bidirectional+no_connect"))
    )
    (net (code "190") (name "unconnected-(U1A-IO_L5P_T0_D06_14-PadR12)") (class "Default")
      (node (ref "U1") (pin "R12") (pinfunction "IO_L5P_T0_D06_14_R12") (pintype "bidirectional+no_connect"))
    )
    (net (code "191") (name "unconnected-(U1A-IO_L7N_T1_D10_14-PadT18)") (class "Default")
      (node (ref "U1") (pin "T18") (pinfunction "IO_L7N_T1_D10_14_T18") (pintype "bidirectional+no_connect"))
    )
    (net (code "192") (name "unconnected-(U1A-IO_L7P_T1_D09_14-PadR18)") (class "Default")
      (node (ref "U1") (pin "R18") (pinfunction "IO_L7P_T1_D09_14_R18") (pintype "bidirectional+no_connect"))
    )
    (net (code "193") (name "unconnected-(U1A-IO_L9N_T1_DQS_D13_14-PadP18)") (class "Default")
      (node (ref "U1") (pin "P18") (pinfunction "IO_L9N_T1_DQS_D13_14_P18") (pintype "bidirectional+no_connect"))
    )
    (net (code "194") (name "unconnected-(U1A-IO_L9P_T1_DQS_14-PadN17)") (class "Default")
      (node (ref "U1") (pin "N17") (pinfunction "IO_L9P_T1_DQS_14_N17") (pintype "bidirectional+no_connect"))
    )
    (net (code "195") (name "unconnected-(U1A-IO_L10N_T1_D15_14-PadM17)") (class "Default")
      (node (ref "U1") (pin "M17") (pinfunction "IO_L10N_T1_D15_14_M17") (pintype "bidirectional+no_connect"))
    )
    (net (code "196") (name "unconnected-(U1A-IO_L10P_T1_D14_14-PadM16)") (class "Default")
      (node (ref "U1") (pin "M16") (pinfunction "IO_L10P_T1_D14_14_M16") (pintype "bidirectional+no_connect"))
    )
    (net (code "197") (name "unconnected-(U1A-IO_L11N_T1_SRCC_14-PadN16)") (class "Default")
      (node (ref "U1") (pin "N16") (pinfunction "IO_L11N_T1_SRCC_14_N16") (pintype "bidirectional+no_connect"))
    )
    (net (code "198") (name "unconnected-(U1A-IO_L12N_T1_MRCC_14-PadR17)") (class "Default")
      (node (ref "U1") (pin "R17") (pinfunction "IO_L12N_T1_MRCC_14_R17") (pintype "bidirectional+no_connect"))
    )
    (net (code "199") (name "unconnected-(U1A-IO_L12P_T1_MRCC_14-PadP17)") (class "Default")
      (node (ref "U1") (pin "P17") (pinfunction "IO_L12P_T1_MRCC_14_P17") (pintype "bidirectional+no_connect"))
    )
    (net (code "200") (name "unconnected-(U1A-IO_L13N_T2_MRCC_14-PadR15)") (class "Default")
      (node (ref "U1") (pin "R15") (pinfunction "IO_L13N_T2_MRCC_14_R15") (pintype "bidirectional+no_connect"))
    )
    (net (code "201") (name "unconnected-(U1A-IO_L14N_T2_SRCC_14-PadT15)") (class "Default")
      (node (ref "U1") (pin "T15") (pinfunction "IO_L14N_T2_SRCC_14_T15") (pintype "bidirectional+no_connect"))
    )
    (net (code "202") (name "unconnected-(U1A-IO_L15N_T2_DQS_DOUT_CSO_B_14-PadT16)") (class "Default")
      (node (ref "U1") (pin "T16") (pinfunction "IO_L15N_T2_DQS_DOUT_CSO_B_14_T16") (pintype "bidirectional+no_connect"))
    )
    (net (code "203") (name "unconnected-(U1A-IO_L15P_T2_DQS_RDWR_B_14-PadR16)") (class "Default")
      (node (ref "U1") (pin "R16") (pinfunction "IO_L15P_T2_DQS_RDWR_B_14_R16") (pintype "bidirectional+no_connect"))
    )
    (net (code "204") (name "unconnected-(U1A-IO_L16N_T2_A15_D31_14-PadV16)") (class "Default")
      (node (ref "U1") (pin "V16") (pinfunction "IO_L16N_T2_A15_D31_14_V16") (pintype "bidirectional+no_connect"))
    )
    (net (code "205") (name "unconnected-(U1A-IO_L16P_T2_CSI_B_14-PadV15)") (class "Default")
      (node (ref "U1") (pin "V15") (pinfunction "IO_L16P_T2_CSI_B_14_V15") (pintype "bidirectional+no_connect"))
    )
    (net (code "206") (name "unconnected-(U1A-IO_L17N_T2_A13_D29_14-PadU18)") (class "Default")
      (node (ref "U1") (pin "U18") (pinfunction "IO_L17N_T2_A13_D29_14_U18") (pintype "bidirectional+no_connect"))
    )
    (net (code "207") (name "unconnected-(U1A-IO_L17P_T2_A14_D30_14-PadU17)") (class "Default")
      (node (ref "U1") (pin "U17") (pinfunction "IO_L17P_T2_A14_D30_14_U17") (pintype "bidirectional+no_connect"))
    )
    (net (code "208") (name "unconnected-(U1A-IO_L18N_T2_A11_D27_14-PadV17)") (class "Default")
      (node (ref "U1") (pin "V17") (pinfunction "IO_L18N_T2_A11_D27_14_V17") (pintype "bidirectional+no_connect"))
    )
    (net (code "209") (name "unconnected-(U1A-IO_L18P_T2_A12_D28_14-PadU16)") (class "Default")
      (node (ref "U1") (pin "U16") (pinfunction "IO_L18P_T2_A12_D28_14_U16") (pintype "bidirectional+no_connect"))
    )
    (net (code "210") (name "unconnected-(U1A-IO_L22N_T3_A04_D20_14-PadV14)") (class "Default")
      (node (ref "U1") (pin "V14") (pinfunction "IO_L22N_T3_A04_D20_14_V14") (pintype "bidirectional+no_connect"))
    )
    (net (code "211") (name "unconnected-(U1A-IO_L22P_T3_A05_D21_14-PadU14)") (class "Default")
      (node (ref "U1") (pin "U14") (pinfunction "IO_L22P_T3_A05_D21_14_U14") (pintype "bidirectional+no_connect"))
    )
    (net (code "212") (name "unconnected-(U1A-IO_L23N_T3_A02_D18_14-PadU13)") (class "Default")
      (node (ref "U1") (pin "U13") (pinfunction "IO_L23N_T3_A02_D18_14_U13") (pintype "bidirectional+no_connect"))
    )
    (net (code "213") (name "unconnected-(U1A-IO_L23P_T3_A03_D19_14-PadT13)") (class "Default")
      (node (ref "U1") (pin "T13") (pinfunction "IO_L23P_T3_A03_D19_14_T13") (pintype "bidirectional+no_connect"))
    )
    (net (code "214") (name "unconnected-(U1B-IO_L14P_T2_SRCC_15-PadF15)") (class "Default")
      (node (ref "U1") (pin "F15") (pinfunction "IO_L14P_T2_SRCC_15_F15") (pintype "bidirectional+no_connect"))
    )
    (net (code "215") (name "unconnected-(U1B-IO_L15P_T2_DQS_15-PadH14)") (class "Default")
      (node (ref "U1") (pin "H14") (pinfunction "IO_L15P_T2_DQS_15_H14") (pintype "bidirectional+no_connect"))
    )
    (net (code "216") (name "unconnected-(U1B-IO_L23N_T3_FWE_B_15-PadJ18)") (class "Default")
      (node (ref "U1") (pin "J18") (pinfunction "IO_L23N_T3_FWE_B_15_J18") (pintype "bidirectional+no_connect"))
    )
    (net (code "217") (name "unconnected-(U1B-IO_L24P_T3_RS1_15-PadK15)") (class "Default")
      (node (ref "U1") (pin "K15") (pinfunction "IO_L24P_T3_RS1_15_K15") (pintype "bidirectional+no_connect"))
    )
    (net (code "218") (name "unconnected-(U1D-IO_L1N_T0_34-PadM1)") (class "Default")
      (node (ref "U1") (pin "M1") (pinfunction "IO_L1N_T0_34_M1") (pintype "bidirectional+no_connect"))
    )
    (net (code "219") (name "unconnected-(U1D-IO_L3N_T0_DQS_34-PadN1)") (class "Default")
      (node (ref "U1") (pin "N1") (pinfunction "IO_L3N_T0_DQS_34_N1") (pintype "bidirectional+no_connect"))
    )
    (net (code "220") (name "unconnected-(U1D-IO_L3P_T0_DQS_34-PadN2)") (class "Default")
      (node (ref "U1") (pin "N2") (pinfunction "IO_L3P_T0_DQS_34_N2") (pintype "bidirectional+no_connect"))
    )
    (net (code "221") (name "unconnected-(U1D-IO_L4N_T0_34-PadM2)") (class "Default")
      (node (ref "U1") (pin "M2") (pinfunction "IO_L4N_T0_34_M2") (pintype "bidirectional+no_connect"))
    )
    (net (code "222") (name "unconnected-(U1D-IO_L4P_T0_34-PadM3)") (class "Default")
      (node (ref "U1") (pin "M3") (pinfunction "IO_L4P_T0_34_M3") (pintype "bidirectional+no_connect"))
    )
    (net (code "223") (name "unconnected-(U1D-IO_L5N_T0_34-PadL4)") (class "Default")
      (node (ref "U1") (pin "L4") (pinfunction "IO_L5N_T0_34_L4") (pintype "bidirectional+no_connect"))
    )
    (net (code "224") (name "unconnected-(U1D-IO_L6N_T0_VREF_34-PadL5)") (class "Default")
      (node (ref "U1") (pin "L5") (pinfunction "IO_L6N_T0_VREF_34_L5") (pintype "bidirectional+no_connect"))
    )
    (net (code "225") (name "unconnected-(U1D-IO_L8P_T1_34-PadU4)") (class "Default")
      (node (ref "U1") (pin "U4") (pinfunction "IO_L8P_T1_34_U4") (pintype "bidirectional+no_connect"))
    )
    (net (code "226") (name "unconnected-(U1D-IO_L10P_T1_34-PadV5)") (class "Default")
      (node (ref "U1") (pin "V5") (pinfunction "IO_L10P_T1_34_V5") (pintype "bidirectional+no_connect"))
    )
    (net (code "227") (name "unconnected-(U1D-IO_L11P_T1_SRCC_34-PadR3)") (class "Default")
      (node (ref "U1") (pin "R3") (pinfunction "IO_L11P_T1_SRCC_34_R3") (pintype "bidirectional+no_connect"))
    )
    (net (code "228") (name "unconnected-(U1D-IO_L12N_T1_MRCC_34-PadT4)") (class "Default")
      (node (ref "U1") (pin "T4") (pinfunction "IO_L12N_T1_MRCC_34_T4") (pintype "bidirectional+no_connect"))
    )
    (net (code "229") (name "unconnected-(U1D-IO_L12P_T1_MRCC_34-PadT5)") (class "Default")
      (node (ref "U1") (pin "T5") (pinfunction "IO_L12P_T1_MRCC_34_T5") (pintype "bidirectional+no_connect"))
    )
    (net (code "230") (name "unconnected-(U1D-IO_L14N_T2_SRCC_34-PadP3)") (class "Default")
      (node (ref "U1") (pin "P3") (pinfunction "IO_L14N_T2_SRCC_34_P3") (pintype "bidirectional+no_connect"))
    )
    (net (code "231") (name "unconnected-(U1D-IO_L14P_T2_SRCC_34-PadP4)") (class "Default")
      (node (ref "U1") (pin "P4") (pinfunction "IO_L14P_T2_SRCC_34_P4") (pintype "bidirectional+no_connect"))
    )
    (net (code "232") (name "unconnected-(U1D-IO_L15N_T2_DQS_34-PadR2)") (class "Default")
      (node (ref "U1") (pin "R2") (pinfunction "IO_L15N_T2_DQS_34_R2") (pintype "bidirectional+no_connect"))
    )
    (net (code "233") (name "unconnected-(U1D-IO_L15P_T2_DQS_34-PadP2)") (class "Default")
      (node (ref "U1") (pin "P2") (pinfunction "IO_L15P_T2_DQS_34_P2") (pintype "bidirectional+no_connect"))
    )
    (net (code "234") (name "unconnected-(U1D-IO_L16N_T2_34-PadN4)") (class "Default")
      (node (ref "U1") (pin "N4") (pinfunction "IO_L16N_T2_34_N4") (pintype "bidirectional+no_connect"))
    )
    (net (code "235") (name "unconnected-(U1D-IO_L16P_T2_34-PadM4)") (class "Default")
      (node (ref "U1") (pin "M4") (pinfunction "IO_L16P_T2_34_M4") (pintype "bidirectional+no_connect"))
    )
    (net (code "236") (name "unconnected-(U1D-IO_L17N_T2_34-PadT1)") (class "Default")
      (node (ref "U1") (pin "T1") (pinfunction "IO_L17N_T2_34_T1") (pintype "bidirectional+no_connect"))
    )
    (net (code "237") (name "unconnected-(U1D-IO_L17P_T2_34-PadR1)") (class "Default")
      (node (ref "U1") (pin "R1") (pinfunction "IO_L17P_T2_34_R1") (pintype "bidirectional+no_connect"))
    )
    (net (code "238") (name "unconnected-(U1D-IO_L19N_T3_VREF_34-PadR5)") (class "Default")
      (node (ref "U1") (pin "R5") (pinfunction "IO_L19N_T3_VREF_34_R5") (pintype "bidirectional+no_connect"))
    )
    (net (code "239") (name "unconnected-(U1D-IO_L19P_T3_34-PadR6)") (class "Default")
      (node (ref "U1") (pin "R6") (pinfunction "IO_L19P_T3_34_R6") (pintype "bidirectional+no_connect"))
    )
    (net (code "240") (name "unconnected-(U1D-IO_L23N_T3_34-PadT6)") (class "Default")
      (node (ref "U1") (pin "T6") (pinfunction "IO_L23N_T3_34_T6") (pintype "bidirectional+no_connect"))
    )
  )
)
